# SSS_SOB_REPRO.net
KiCad netlist of a schematic drawn in EAGLE
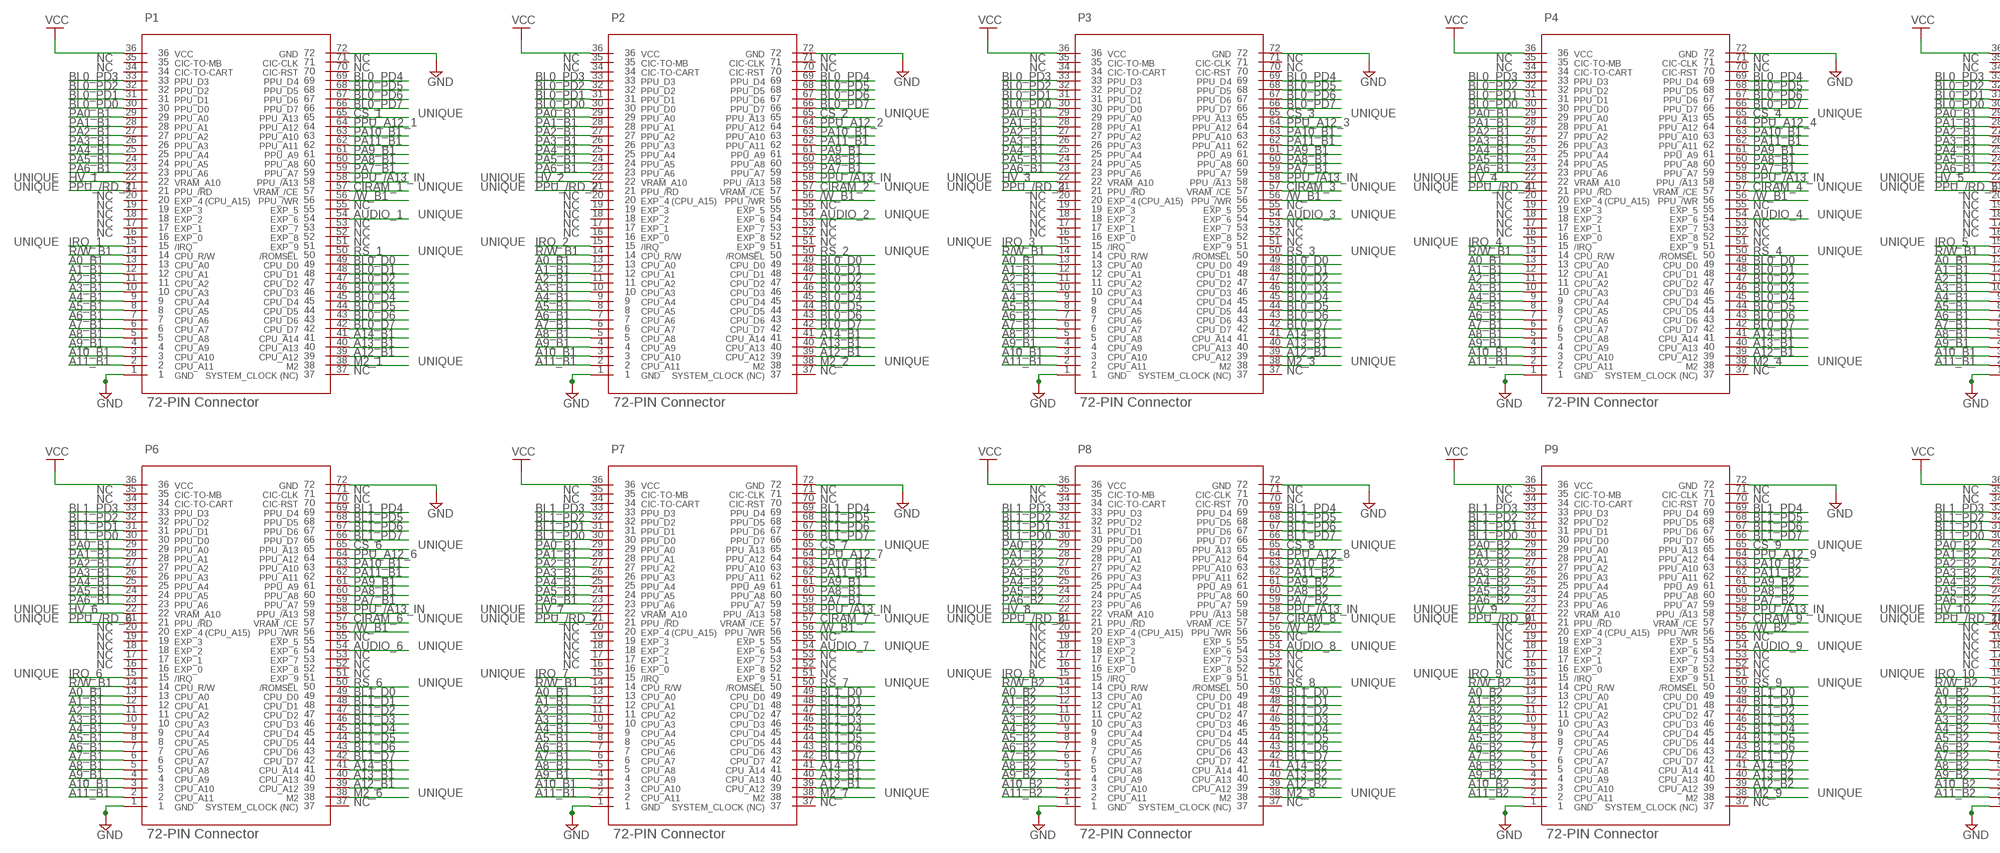
[diagram p0: schematic, sheet 1, part 1 of 3]
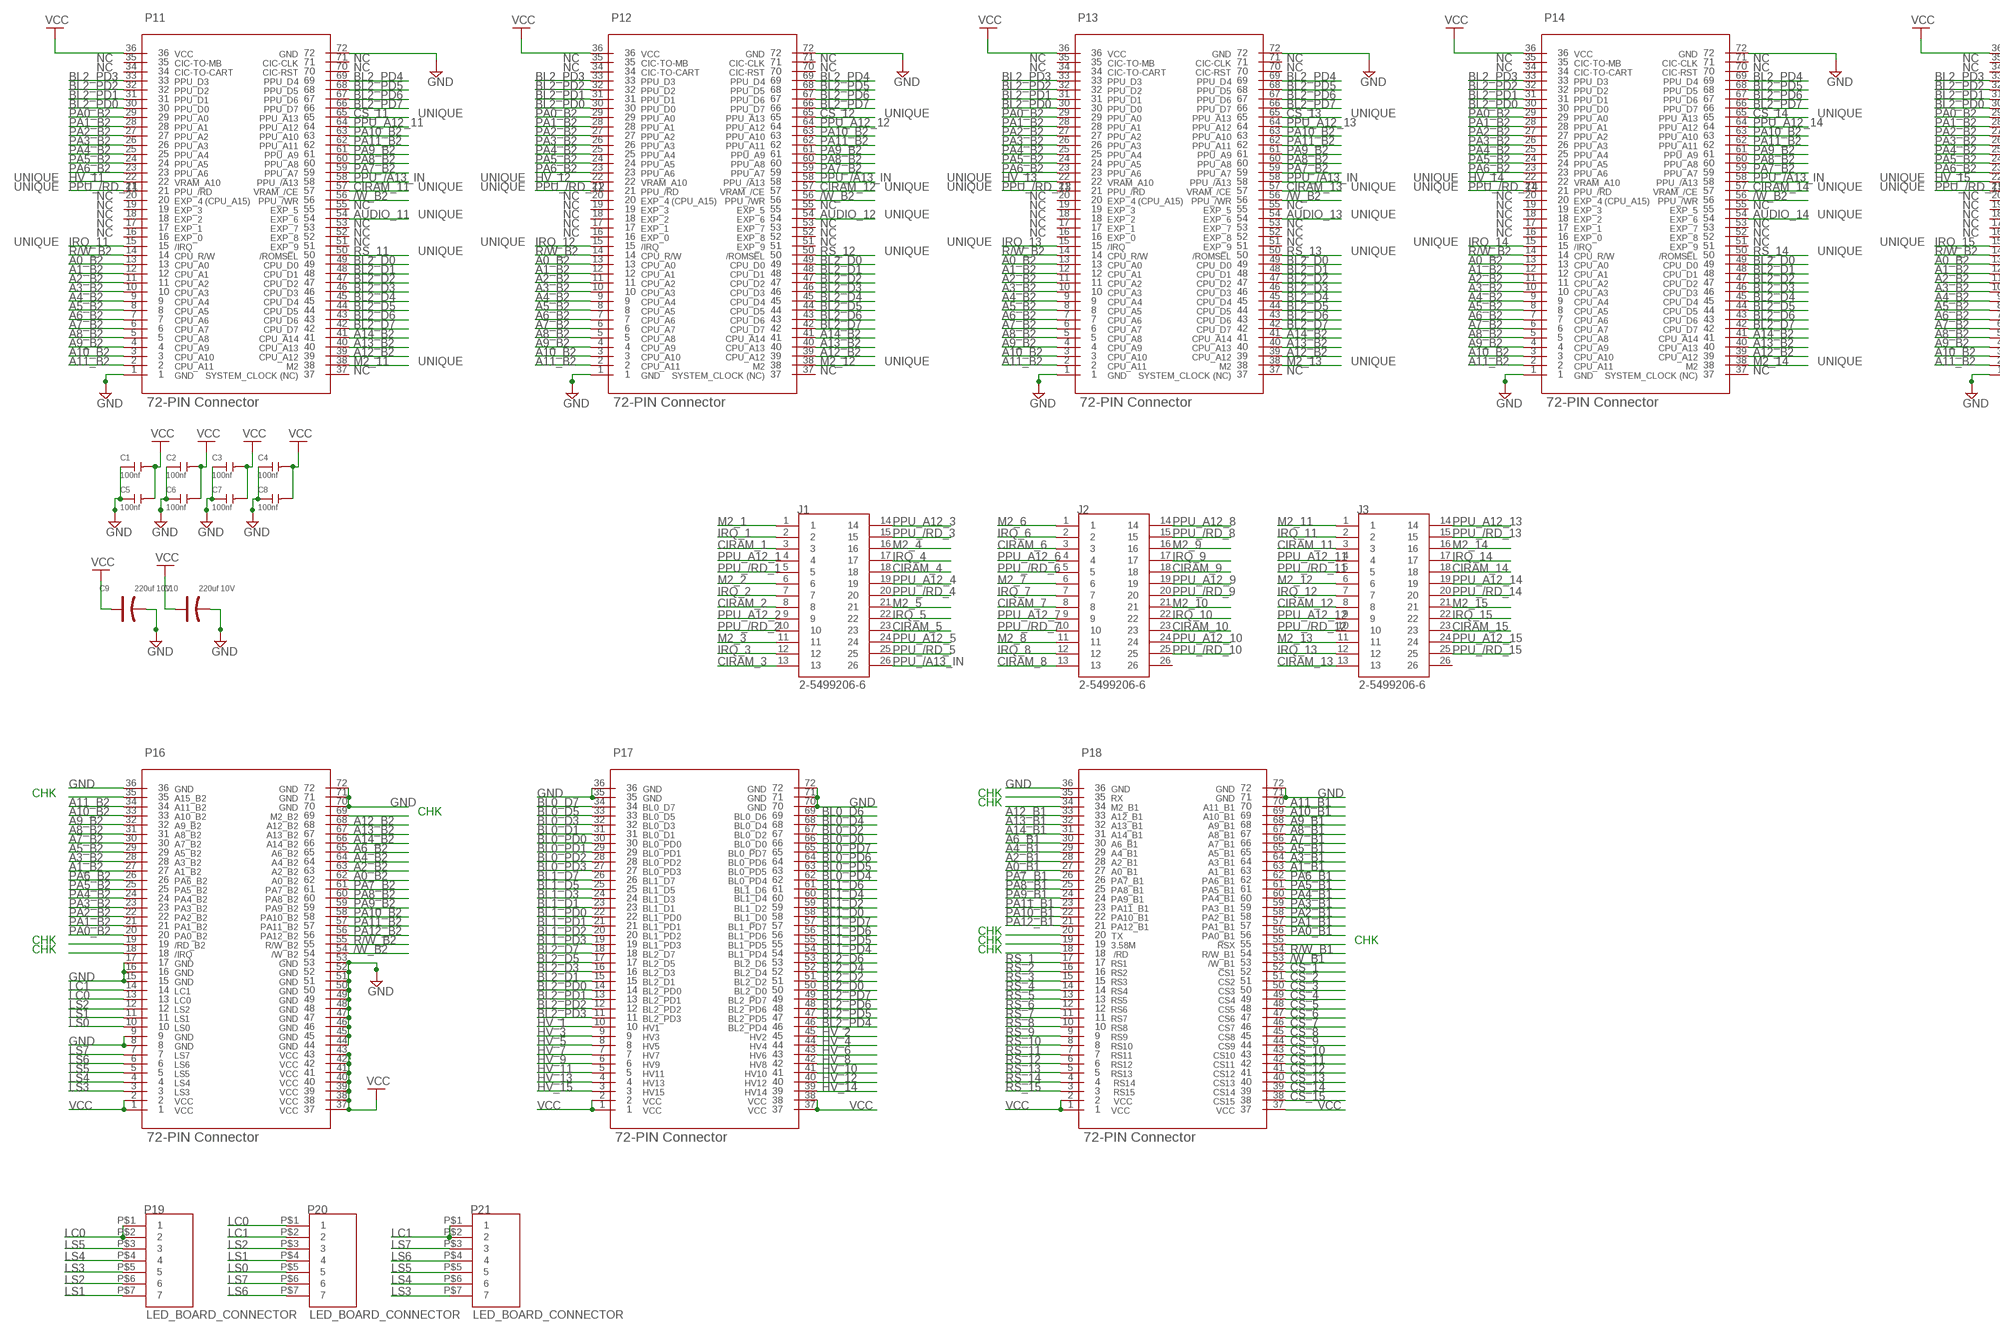
[diagram p1: schematic, sheet 1, part 2 of 3]
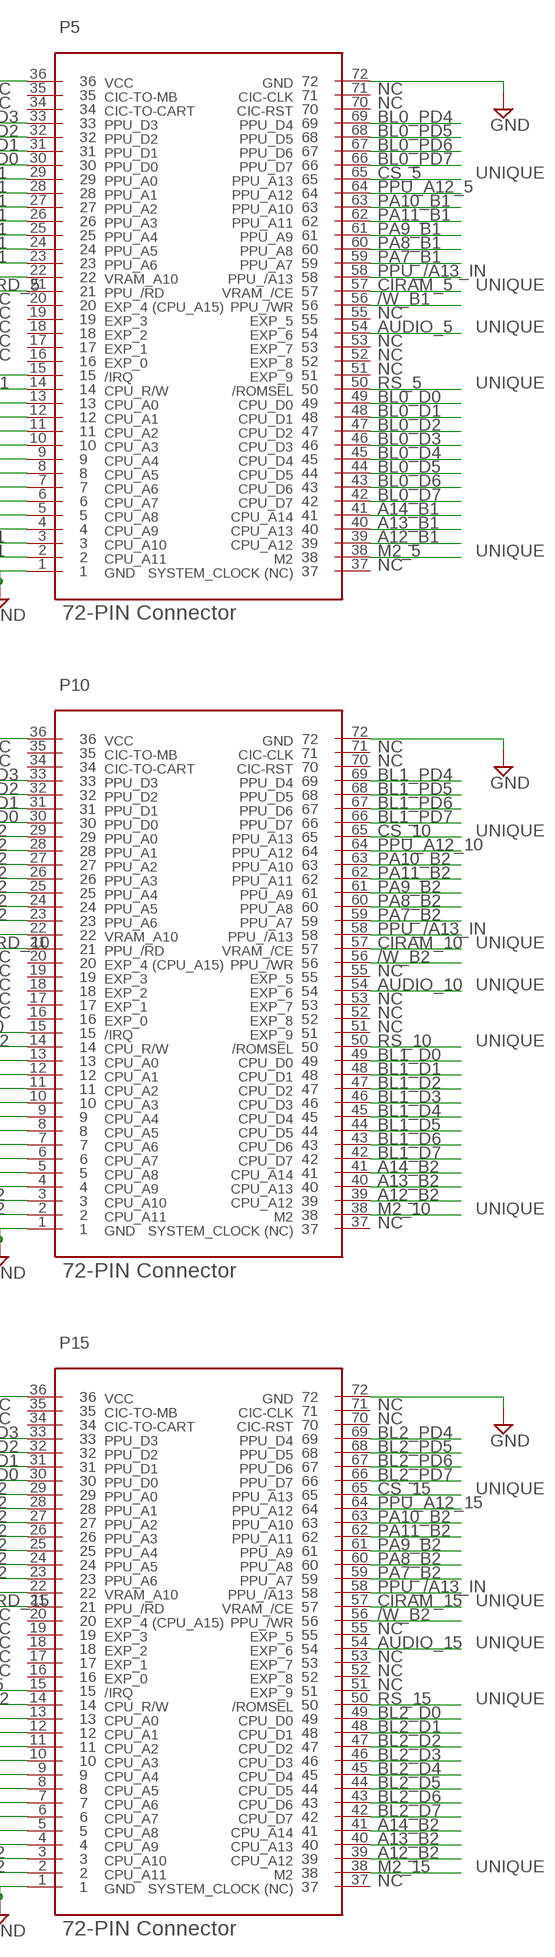
[diagram p2: schematic, sheet 1, part 3 of 3]

(export (version "E")
  (design (tool "Eeschema 10.0.6"))
  (components
    (comp (ref "C1")
      (value "100nf")
      (footprint "eagle-import:C0603")
      (fields (field (name "MPN") "CC0603KRX7R9BB104"))
      (libsource (lib "eagle-import") (part "CERAMIC-100NF-50V-10%-X7R(0603)"))
    )
    (comp (ref "C2")
      (value "100nf")
      (footprint "eagle-import:C0603")
      (fields (field (name "MPN") "CC0603KRX7R9BB104"))
      (libsource (lib "eagle-import") (part "CERAMIC-100NF-50V-10%-X7R(0603)"))
    )
    (comp (ref "C3")
      (value "100nf")
      (footprint "eagle-import:C0603")
      (fields (field (name "MPN") "CC0603KRX7R9BB104"))
      (libsource (lib "eagle-import") (part "CERAMIC-100NF-50V-10%-X7R(0603)"))
    )
    (comp (ref "C4")
      (value "100nf")
      (footprint "eagle-import:C0603")
      (fields (field (name "MPN") "CC0603KRX7R9BB104"))
      (libsource (lib "eagle-import") (part "CERAMIC-100NF-50V-10%-X7R(0603)"))
    )
    (comp (ref "C5")
      (value "100nf")
      (footprint "eagle-import:C0603")
      (fields (field (name "MPN") "CC0603KRX7R9BB104"))
      (libsource (lib "eagle-import") (part "CERAMIC-100NF-50V-10%-X7R(0603)"))
    )
    (comp (ref "C6")
      (value "100nf")
      (footprint "eagle-import:C0603")
      (fields (field (name "MPN") "CC0603KRX7R9BB104"))
      (libsource (lib "eagle-import") (part "CERAMIC-100NF-50V-10%-X7R(0603)"))
    )
    (comp (ref "C7")
      (value "100nf")
      (footprint "eagle-import:C0603")
      (fields (field (name "MPN") "CC0603KRX7R9BB104"))
      (libsource (lib "eagle-import") (part "CERAMIC-100NF-50V-10%-X7R(0603)"))
    )
    (comp (ref "C8")
      (value "100nf")
      (footprint "eagle-import:C0603")
      (fields (field (name "MPN") "CC0603KRX7R9BB104"))
      (libsource (lib "eagle-import") (part "CERAMIC-100NF-50V-10%-X7R(0603)"))
    )
    (comp (ref "C9")
      (value "220uf 10V")
      (footprint "eagle-import:PC-D5.3MM")
      (fields (field (name "MPN") "KS 100uF/16V"))
      (libsource (lib "eagle-import") (part "DIP-ALUMINUM-100UF-16V(D5-H7MM)"))
    )
    (comp (ref "C10")
      (value "220uf 10V")
      (footprint "eagle-import:PC-D5.3MM")
      (fields (field (name "MPN") "KS 100uF/16V"))
      (libsource (lib "eagle-import") (part "DIP-ALUMINUM-100UF-16V(D5-H7MM)"))
    )
    (comp (ref "J1")
      (value "2-5499206-6")
      (footprint "eagle-import:TE_2-5499206-6")
      (fields (field (name "MF") "TE Connectivity"))
      (libsource (lib "eagle-import") (part "2-5499206-6"))
    )
    (comp (ref "J2")
      (value "2-5499206-6")
      (footprint "eagle-import:TE_2-5499206-6")
      (fields (field (name "MF") "TE Connectivity"))
      (libsource (lib "eagle-import") (part "2-5499206-6"))
    )
    (comp (ref "J3")
      (value "2-5499206-6")
      (footprint "eagle-import:TE_2-5499206-6")
      (fields (field (name "MF") "TE Connectivity"))
      (libsource (lib "eagle-import") (part "2-5499206-6"))
    )
    (comp (ref "P1")
      (value "CARTRIDGE_CONNECTOR")
      (footprint "eagle-import:72PIN")
      (libsource (lib "eagle-import") (part "CARTRIDGE_CONNECTOR"))
    )
    (comp (ref "P2")
      (value "CARTRIDGE_CONNECTOR")
      (footprint "eagle-import:72PIN")
      (libsource (lib "eagle-import") (part "CARTRIDGE_CONNECTOR"))
    )
    (comp (ref "P3")
      (value "CARTRIDGE_CONNECTOR")
      (footprint "eagle-import:72PIN")
      (libsource (lib "eagle-import") (part "CARTRIDGE_CONNECTOR"))
    )
    (comp (ref "P4")
      (value "CARTRIDGE_CONNECTOR")
      (footprint "eagle-import:72PIN")
      (libsource (lib "eagle-import") (part "CARTRIDGE_CONNECTOR"))
    )
    (comp (ref "P5")
      (value "CARTRIDGE_CONNECTOR")
      (footprint "eagle-import:72PIN")
      (libsource (lib "eagle-import") (part "CARTRIDGE_CONNECTOR"))
    )
    (comp (ref "P6")
      (value "CARTRIDGE_CONNECTOR")
      (footprint "eagle-import:72PIN")
      (libsource (lib "eagle-import") (part "CARTRIDGE_CONNECTOR"))
    )
    (comp (ref "P7")
      (value "CARTRIDGE_CONNECTOR")
      (footprint "eagle-import:72PIN")
      (libsource (lib "eagle-import") (part "CARTRIDGE_CONNECTOR"))
    )
    (comp (ref "P8")
      (value "CARTRIDGE_CONNECTOR")
      (footprint "eagle-import:72PIN")
      (libsource (lib "eagle-import") (part "CARTRIDGE_CONNECTOR"))
    )
    (comp (ref "P9")
      (value "CARTRIDGE_CONNECTOR")
      (footprint "eagle-import:72PIN")
      (libsource (lib "eagle-import") (part "CARTRIDGE_CONNECTOR"))
    )
    (comp (ref "P10")
      (value "CARTRIDGE_CONNECTOR")
      (footprint "eagle-import:72PIN")
      (libsource (lib "eagle-import") (part "CARTRIDGE_CONNECTOR"))
    )
    (comp (ref "P11")
      (value "CARTRIDGE_CONNECTOR")
      (footprint "eagle-import:72PIN")
      (libsource (lib "eagle-import") (part "CARTRIDGE_CONNECTOR"))
    )
    (comp (ref "P12")
      (value "CARTRIDGE_CONNECTOR")
      (footprint "eagle-import:72PIN")
      (libsource (lib "eagle-import") (part "CARTRIDGE_CONNECTOR"))
    )
    (comp (ref "P13")
      (value "CARTRIDGE_CONNECTOR")
      (footprint "eagle-import:72PIN")
      (libsource (lib "eagle-import") (part "CARTRIDGE_CONNECTOR"))
    )
    (comp (ref "P14")
      (value "CARTRIDGE_CONNECTOR")
      (footprint "eagle-import:72PIN")
      (libsource (lib "eagle-import") (part "CARTRIDGE_CONNECTOR"))
    )
    (comp (ref "P15")
      (value "CARTRIDGE_CONNECTOR")
      (footprint "eagle-import:72PIN")
      (libsource (lib "eagle-import") (part "CARTRIDGE_CONNECTOR"))
    )
    (comp (ref "P16")
      (value "P16_CONNECTOR")
      (footprint "eagle-import:72PIN")
      (libsource (lib "eagle-import") (part "P16_CONNECTOR"))
    )
    (comp (ref "P17")
      (value "P17_CONNECTOR")
      (footprint "eagle-import:72PIN")
      (libsource (lib "eagle-import") (part "P17_CONNECTOR"))
    )
    (comp (ref "P18")
      (value "P18_CONNECTOR")
      (footprint "eagle-import:72PIN")
      (libsource (lib "eagle-import") (part "P18_CONNECTOR"))
    )
    (comp (ref "P19")
      (value "LED_BOARD_CONNECTOR")
      (footprint "eagle-import:7PIN_LED")
      (libsource (lib "eagle-import") (part "LED_BOARD_CONNECTOR"))
    )
    (comp (ref "P20")
      (value "LED_BOARD_CONNECTOR")
      (footprint "eagle-import:7PIN_LED")
      (libsource (lib "eagle-import") (part "LED_BOARD_CONNECTOR"))
    )
    (comp (ref "P21")
      (value "LED_BOARD_CONNECTOR")
      (footprint "eagle-import:7PIN_LED")
      (libsource (lib "eagle-import") (part "LED_BOARD_CONNECTOR"))
    )
  )
  (nets
    (net (code "1") (name "/A0_B1") (class "Default")
      (node (ref "P1") (pin "13") (pinfunction "13_13") (pintype "bidirectional"))
      (node (ref "P18") (pin "27") (pinfunction "27_27") (pintype "bidirectional"))
      (node (ref "P2") (pin "13") (pinfunction "13_13") (pintype "bidirectional"))
      (node (ref "P3") (pin "13") (pinfunction "13_13") (pintype "bidirectional"))
      (node (ref "P4") (pin "13") (pinfunction "13_13") (pintype "bidirectional"))
      (node (ref "P5") (pin "13") (pinfunction "13_13") (pintype "bidirectional"))
      (node (ref "P6") (pin "13") (pinfunction "13_13") (pintype "bidirectional"))
      (node (ref "P7") (pin "13") (pinfunction "13_13") (pintype "bidirectional"))
    )
    (net (code "2") (name "/A0_B2") (class "Default")
      (node (ref "P10") (pin "13") (pinfunction "13_13") (pintype "bidirectional"))
      (node (ref "P11") (pin "13") (pinfunction "13_13") (pintype "bidirectional"))
      (node (ref "P12") (pin "13") (pinfunction "13_13") (pintype "bidirectional"))
      (node (ref "P13") (pin "13") (pinfunction "13_13") (pintype "bidirectional"))
      (node (ref "P14") (pin "13") (pinfunction "13_13") (pintype "bidirectional"))
      (node (ref "P15") (pin "13") (pinfunction "13_13") (pintype "bidirectional"))
      (node (ref "P16") (pin "62") (pinfunction "62_62") (pintype "bidirectional"))
      (node (ref "P8") (pin "13") (pinfunction "13_13") (pintype "bidirectional"))
      (node (ref "P9") (pin "13") (pinfunction "13_13") (pintype "bidirectional"))
    )
    (net (code "3") (name "/A1_B1") (class "Default")
      (node (ref "P1") (pin "12") (pinfunction "12_12") (pintype "bidirectional"))
      (node (ref "P18") (pin "63") (pinfunction "63_63") (pintype "bidirectional"))
      (node (ref "P2") (pin "12") (pinfunction "12_12") (pintype "bidirectional"))
      (node (ref "P3") (pin "12") (pinfunction "12_12") (pintype "bidirectional"))
      (node (ref "P4") (pin "12") (pinfunction "12_12") (pintype "bidirectional"))
      (node (ref "P5") (pin "12") (pinfunction "12_12") (pintype "bidirectional"))
      (node (ref "P6") (pin "12") (pinfunction "12_12") (pintype "bidirectional"))
      (node (ref "P7") (pin "12") (pinfunction "12_12") (pintype "bidirectional"))
    )
    (net (code "4") (name "/A1_B2") (class "Default")
      (node (ref "P10") (pin "12") (pinfunction "12_12") (pintype "bidirectional"))
      (node (ref "P11") (pin "12") (pinfunction "12_12") (pintype "bidirectional"))
      (node (ref "P12") (pin "12") (pinfunction "12_12") (pintype "bidirectional"))
      (node (ref "P13") (pin "12") (pinfunction "12_12") (pintype "bidirectional"))
      (node (ref "P14") (pin "12") (pinfunction "12_12") (pintype "bidirectional"))
      (node (ref "P15") (pin "12") (pinfunction "12_12") (pintype "bidirectional"))
      (node (ref "P16") (pin "27") (pinfunction "27_27") (pintype "bidirectional"))
      (node (ref "P8") (pin "12") (pinfunction "12_12") (pintype "bidirectional"))
      (node (ref "P9") (pin "12") (pinfunction "12_12") (pintype "bidirectional"))
    )
    (net (code "5") (name "/A2_B1") (class "Default")
      (node (ref "P1") (pin "11") (pinfunction "11_11") (pintype "bidirectional"))
      (node (ref "P18") (pin "28") (pinfunction "28_28") (pintype "bidirectional"))
      (node (ref "P2") (pin "11") (pinfunction "11_11") (pintype "bidirectional"))
      (node (ref "P3") (pin "11") (pinfunction "11_11") (pintype "bidirectional"))
      (node (ref "P4") (pin "11") (pinfunction "11_11") (pintype "bidirectional"))
      (node (ref "P5") (pin "11") (pinfunction "11_11") (pintype "bidirectional"))
      (node (ref "P6") (pin "11") (pinfunction "11_11") (pintype "bidirectional"))
      (node (ref "P7") (pin "11") (pinfunction "11_11") (pintype "bidirectional"))
    )
    (net (code "6") (name "/A2_B2") (class "Default")
      (node (ref "P10") (pin "11") (pinfunction "11_11") (pintype "bidirectional"))
      (node (ref "P11") (pin "11") (pinfunction "11_11") (pintype "bidirectional"))
      (node (ref "P12") (pin "11") (pinfunction "11_11") (pintype "bidirectional"))
      (node (ref "P13") (pin "11") (pinfunction "11_11") (pintype "bidirectional"))
      (node (ref "P14") (pin "11") (pinfunction "11_11") (pintype "bidirectional"))
      (node (ref "P15") (pin "11") (pinfunction "11_11") (pintype "bidirectional"))
      (node (ref "P16") (pin "63") (pinfunction "63_63") (pintype "bidirectional"))
      (node (ref "P8") (pin "11") (pinfunction "11_11") (pintype "bidirectional"))
      (node (ref "P9") (pin "11") (pinfunction "11_11") (pintype "bidirectional"))
    )
    (net (code "7") (name "/A3_B1") (class "Default")
      (node (ref "P1") (pin "10") (pinfunction "10_10") (pintype "bidirectional"))
      (node (ref "P18") (pin "64") (pinfunction "64_64") (pintype "bidirectional"))
      (node (ref "P2") (pin "10") (pinfunction "10_10") (pintype "bidirectional"))
      (node (ref "P3") (pin "10") (pinfunction "10_10") (pintype "bidirectional"))
      (node (ref "P4") (pin "10") (pinfunction "10_10") (pintype "bidirectional"))
      (node (ref "P5") (pin "10") (pinfunction "10_10") (pintype "bidirectional"))
      (node (ref "P6") (pin "10") (pinfunction "10_10") (pintype "bidirectional"))
      (node (ref "P7") (pin "10") (pinfunction "10_10") (pintype "bidirectional"))
    )
    (net (code "8") (name "/A3_B2") (class "Default")
      (node (ref "P10") (pin "10") (pinfunction "10_10") (pintype "bidirectional"))
      (node (ref "P11") (pin "10") (pinfunction "10_10") (pintype "bidirectional"))
      (node (ref "P12") (pin "10") (pinfunction "10_10") (pintype "bidirectional"))
      (node (ref "P13") (pin "10") (pinfunction "10_10") (pintype "bidirectional"))
      (node (ref "P14") (pin "10") (pinfunction "10_10") (pintype "bidirectional"))
      (node (ref "P15") (pin "10") (pinfunction "10_10") (pintype "bidirectional"))
      (node (ref "P16") (pin "28") (pinfunction "28_28") (pintype "bidirectional"))
      (node (ref "P8") (pin "10") (pinfunction "10_10") (pintype "bidirectional"))
      (node (ref "P9") (pin "10") (pinfunction "10_10") (pintype "bidirectional"))
    )
    (net (code "9") (name "/A4_B1") (class "Default")
      (node (ref "P1") (pin "9") (pinfunction "9_9") (pintype "bidirectional"))
      (node (ref "P18") (pin "29") (pinfunction "29_29") (pintype "bidirectional"))
      (node (ref "P2") (pin "9") (pinfunction "9_9") (pintype "bidirectional"))
      (node (ref "P3") (pin "9") (pinfunction "9_9") (pintype "bidirectional"))
      (node (ref "P4") (pin "9") (pinfunction "9_9") (pintype "bidirectional"))
      (node (ref "P5") (pin "9") (pinfunction "9_9") (pintype "bidirectional"))
      (node (ref "P6") (pin "9") (pinfunction "9_9") (pintype "bidirectional"))
      (node (ref "P7") (pin "9") (pinfunction "9_9") (pintype "bidirectional"))
    )
    (net (code "10") (name "/A4_B2") (class "Default")
      (node (ref "P10") (pin "9") (pinfunction "9_9") (pintype "bidirectional"))
      (node (ref "P11") (pin "9") (pinfunction "9_9") (pintype "bidirectional"))
      (node (ref "P12") (pin "9") (pinfunction "9_9") (pintype "bidirectional"))
      (node (ref "P13") (pin "9") (pinfunction "9_9") (pintype "bidirectional"))
      (node (ref "P14") (pin "9") (pinfunction "9_9") (pintype "bidirectional"))
      (node (ref "P15") (pin "9") (pinfunction "9_9") (pintype "bidirectional"))
      (node (ref "P16") (pin "64") (pinfunction "64_64") (pintype "bidirectional"))
      (node (ref "P8") (pin "9") (pinfunction "9_9") (pintype "bidirectional"))
      (node (ref "P9") (pin "9") (pinfunction "9_9") (pintype "bidirectional"))
    )
    (net (code "11") (name "/A5_B1") (class "Default")
      (node (ref "P1") (pin "8") (pinfunction "8_8") (pintype "bidirectional"))
      (node (ref "P18") (pin "65") (pinfunction "65_65") (pintype "bidirectional"))
      (node (ref "P2") (pin "8") (pinfunction "8_8") (pintype "bidirectional"))
      (node (ref "P3") (pin "8") (pinfunction "8_8") (pintype "bidirectional"))
      (node (ref "P4") (pin "8") (pinfunction "8_8") (pintype "bidirectional"))
      (node (ref "P5") (pin "8") (pinfunction "8_8") (pintype "bidirectional"))
      (node (ref "P6") (pin "8") (pinfunction "8_8") (pintype "bidirectional"))
      (node (ref "P7") (pin "8") (pinfunction "8_8") (pintype "bidirectional"))
    )
    (net (code "12") (name "/A5_B2") (class "Default")
      (node (ref "P10") (pin "8") (pinfunction "8_8") (pintype "bidirectional"))
      (node (ref "P11") (pin "8") (pinfunction "8_8") (pintype "bidirectional"))
      (node (ref "P12") (pin "8") (pinfunction "8_8") (pintype "bidirectional"))
      (node (ref "P13") (pin "8") (pinfunction "8_8") (pintype "bidirectional"))
      (node (ref "P14") (pin "8") (pinfunction "8_8") (pintype "bidirectional"))
      (node (ref "P15") (pin "8") (pinfunction "8_8") (pintype "bidirectional"))
      (node (ref "P16") (pin "29") (pinfunction "29_29") (pintype "bidirectional"))
      (node (ref "P8") (pin "8") (pinfunction "8_8") (pintype "bidirectional"))
      (node (ref "P9") (pin "8") (pinfunction "8_8") (pintype "bidirectional"))
    )
    (net (code "13") (name "/A6_B1") (class "Default")
      (node (ref "P1") (pin "7") (pinfunction "7_7") (pintype "bidirectional"))
      (node (ref "P18") (pin "30") (pinfunction "30_30") (pintype "bidirectional"))
      (node (ref "P2") (pin "7") (pinfunction "7_7") (pintype "bidirectional"))
      (node (ref "P3") (pin "7") (pinfunction "7_7") (pintype "bidirectional"))
      (node (ref "P4") (pin "7") (pinfunction "7_7") (pintype "bidirectional"))
      (node (ref "P5") (pin "7") (pinfunction "7_7") (pintype "bidirectional"))
      (node (ref "P6") (pin "7") (pinfunction "7_7") (pintype "bidirectional"))
      (node (ref "P7") (pin "7") (pinfunction "7_7") (pintype "bidirectional"))
    )
    (net (code "14") (name "/A6_B2") (class "Default")
      (node (ref "P10") (pin "7") (pinfunction "7_7") (pintype "bidirectional"))
      (node (ref "P11") (pin "7") (pinfunction "7_7") (pintype "bidirectional"))
      (node (ref "P12") (pin "7") (pinfunction "7_7") (pintype "bidirectional"))
      (node (ref "P13") (pin "7") (pinfunction "7_7") (pintype "bidirectional"))
      (node (ref "P14") (pin "7") (pinfunction "7_7") (pintype "bidirectional"))
      (node (ref "P15") (pin "7") (pinfunction "7_7") (pintype "bidirectional"))
      (node (ref "P16") (pin "65") (pinfunction "65_65") (pintype "bidirectional"))
      (node (ref "P8") (pin "7") (pinfunction "7_7") (pintype "bidirectional"))
      (node (ref "P9") (pin "7") (pinfunction "7_7") (pintype "bidirectional"))
    )
    (net (code "15") (name "/A7_B1") (class "Default")
      (node (ref "P1") (pin "6") (pinfunction "6_6") (pintype "bidirectional"))
      (node (ref "P18") (pin "66") (pinfunction "66_66") (pintype "bidirectional"))
      (node (ref "P2") (pin "6") (pinfunction "6_6") (pintype "bidirectional"))
      (node (ref "P3") (pin "6") (pinfunction "6_6") (pintype "bidirectional"))
      (node (ref "P4") (pin "6") (pinfunction "6_6") (pintype "bidirectional"))
      (node (ref "P5") (pin "6") (pinfunction "6_6") (pintype "bidirectional"))
      (node (ref "P6") (pin "6") (pinfunction "6_6") (pintype "bidirectional"))
      (node (ref "P7") (pin "6") (pinfunction "6_6") (pintype "bidirectional"))
    )
    (net (code "16") (name "/A7_B2") (class "Default")
      (node (ref "P10") (pin "6") (pinfunction "6_6") (pintype "bidirectional"))
      (node (ref "P11") (pin "6") (pinfunction "6_6") (pintype "bidirectional"))
      (node (ref "P12") (pin "6") (pinfunction "6_6") (pintype "bidirectional"))
      (node (ref "P13") (pin "6") (pinfunction "6_6") (pintype "bidirectional"))
      (node (ref "P14") (pin "6") (pinfunction "6_6") (pintype "bidirectional"))
      (node (ref "P15") (pin "6") (pinfunction "6_6") (pintype "bidirectional"))
      (node (ref "P16") (pin "30") (pinfunction "30_30") (pintype "bidirectional"))
      (node (ref "P8") (pin "6") (pinfunction "6_6") (pintype "bidirectional"))
      (node (ref "P9") (pin "6") (pinfunction "6_6") (pintype "bidirectional"))
    )
    (net (code "17") (name "/A8_B1") (class "Default")
      (node (ref "P1") (pin "5") (pinfunction "5_5") (pintype "bidirectional"))
      (node (ref "P18") (pin "67") (pinfunction "67_67") (pintype "bidirectional"))
      (node (ref "P2") (pin "5") (pinfunction "5_5") (pintype "bidirectional"))
      (node (ref "P3") (pin "5") (pinfunction "5_5") (pintype "bidirectional"))
      (node (ref "P4") (pin "5") (pinfunction "5_5") (pintype "bidirectional"))
      (node (ref "P5") (pin "5") (pinfunction "5_5") (pintype "bidirectional"))
      (node (ref "P6") (pin "5") (pinfunction "5_5") (pintype "bidirectional"))
      (node (ref "P7") (pin "5") (pinfunction "5_5") (pintype "bidirectional"))
    )
    (net (code "18") (name "/A8_B2") (class "Default")
      (node (ref "P10") (pin "5") (pinfunction "5_5") (pintype "bidirectional"))
      (node (ref "P11") (pin "5") (pinfunction "5_5") (pintype "bidirectional"))
      (node (ref "P12") (pin "5") (pinfunction "5_5") (pintype "bidirectional"))
      (node (ref "P13") (pin "5") (pinfunction "5_5") (pintype "bidirectional"))
      (node (ref "P14") (pin "5") (pinfunction "5_5") (pintype "bidirectional"))
      (node (ref "P15") (pin "5") (pinfunction "5_5") (pintype "bidirectional"))
      (node (ref "P16") (pin "31") (pinfunction "31_31") (pintype "bidirectional"))
      (node (ref "P8") (pin "5") (pinfunction "5_5") (pintype "bidirectional"))
      (node (ref "P9") (pin "5") (pinfunction "5_5") (pintype "bidirectional"))
    )
    (net (code "19") (name "/A9_B1") (class "Default")
      (node (ref "P1") (pin "4") (pinfunction "4_4") (pintype "bidirectional"))
      (node (ref "P18") (pin "68") (pinfunction "68_68") (pintype "bidirectional"))
      (node (ref "P2") (pin "4") (pinfunction "4_4") (pintype "bidirectional"))
      (node (ref "P3") (pin "4") (pinfunction "4_4") (pintype "bidirectional"))
      (node (ref "P4") (pin "4") (pinfunction "4_4") (pintype "bidirectional"))
      (node (ref "P5") (pin "4") (pinfunction "4_4") (pintype "bidirectional"))
      (node (ref "P6") (pin "4") (pinfunction "4_4") (pintype "bidirectional"))
      (node (ref "P7") (pin "4") (pinfunction "4_4") (pintype "bidirectional"))
    )
    (net (code "20") (name "/A9_B2") (class "Default")
      (node (ref "P10") (pin "4") (pinfunction "4_4") (pintype "bidirectional"))
      (node (ref "P11") (pin "4") (pinfunction "4_4") (pintype "bidirectional"))
      (node (ref "P12") (pin "4") (pinfunction "4_4") (pintype "bidirectional"))
      (node (ref "P13") (pin "4") (pinfunction "4_4") (pintype "bidirectional"))
      (node (ref "P14") (pin "4") (pinfunction "4_4") (pintype "bidirectional"))
      (node (ref "P15") (pin "4") (pinfunction "4_4") (pintype "bidirectional"))
      (node (ref "P16") (pin "32") (pinfunction "32_32") (pintype "bidirectional"))
      (node (ref "P8") (pin "4") (pinfunction "4_4") (pintype "bidirectional"))
      (node (ref "P9") (pin "4") (pinfunction "4_4") (pintype "bidirectional"))
    )
    (net (code "21") (name "/A10_B1") (class "Default")
      (node (ref "P1") (pin "3") (pinfunction "3_3") (pintype "bidirectional"))
      (node (ref "P18") (pin "69") (pinfunction "69_69") (pintype "bidirectional"))
      (node (ref "P2") (pin "3") (pinfunction "3_3") (pintype "bidirectional"))
      (node (ref "P3") (pin "3") (pinfunction "3_3") (pintype "bidirectional"))
      (node (ref "P4") (pin "3") (pinfunction "3_3") (pintype "bidirectional"))
      (node (ref "P5") (pin "3") (pinfunction "3_3") (pintype "bidirectional"))
      (node (ref "P6") (pin "3") (pinfunction "3_3") (pintype "bidirectional"))
      (node (ref "P7") (pin "3") (pinfunction "3_3") (pintype "bidirectional"))
    )
    (net (code "22") (name "/A10_B2") (class "Default")
      (node (ref "P10") (pin "3") (pinfunction "3_3") (pintype "bidirectional"))
      (node (ref "P11") (pin "3") (pinfunction "3_3") (pintype "bidirectional"))
      (node (ref "P12") (pin "3") (pinfunction "3_3") (pintype "bidirectional"))
      (node (ref "P13") (pin "3") (pinfunction "3_3") (pintype "bidirectional"))
      (node (ref "P14") (pin "3") (pinfunction "3_3") (pintype "bidirectional"))
      (node (ref "P15") (pin "3") (pinfunction "3_3") (pintype "bidirectional"))
      (node (ref "P16") (pin "33") (pinfunction "33_33") (pintype "bidirectional"))
      (node (ref "P8") (pin "3") (pinfunction "3_3") (pintype "bidirectional"))
      (node (ref "P9") (pin "3") (pinfunction "3_3") (pintype "bidirectional"))
    )
    (net (code "23") (name "/A11_B1") (class "Default")
      (node (ref "P1") (pin "2") (pinfunction "2_2") (pintype "bidirectional"))
      (node (ref "P18") (pin "70") (pinfunction "70_70") (pintype "bidirectional"))
      (node (ref "P2") (pin "2") (pinfunction "2_2") (pintype "bidirectional"))
      (node (ref "P3") (pin "2") (pinfunction "2_2") (pintype "bidirectional"))
      (node (ref "P4") (pin "2") (pinfunction "2_2") (pintype "bidirectional"))
      (node (ref "P5") (pin "2") (pinfunction "2_2") (pintype "bidirectional"))
      (node (ref "P6") (pin "2") (pinfunction "2_2") (pintype "bidirectional"))
      (node (ref "P7") (pin "2") (pinfunction "2_2") (pintype "bidirectional"))
    )
    (net (code "24") (name "/A11_B2") (class "Default")
      (node (ref "P10") (pin "2") (pinfunction "2_2") (pintype "bidirectional"))
      (node (ref "P11") (pin "2") (pinfunction "2_2") (pintype "bidirectional"))
      (node (ref "P12") (pin "2") (pinfunction "2_2") (pintype "bidirectional"))
      (node (ref "P13") (pin "2") (pinfunction "2_2") (pintype "bidirectional"))
      (node (ref "P14") (pin "2") (pinfunction "2_2") (pintype "bidirectional"))
      (node (ref "P15") (pin "2") (pinfunction "2_2") (pintype "bidirectional"))
      (node (ref "P16") (pin "34") (pinfunction "34_34") (pintype "bidirectional"))
      (node (ref "P8") (pin "2") (pinfunction "2_2") (pintype "bidirectional"))
      (node (ref "P9") (pin "2") (pinfunction "2_2") (pintype "bidirectional"))
    )
    (net (code "25") (name "/A12_B1") (class "Default")
      (node (ref "P1") (pin "39") (pinfunction "39_39") (pintype "bidirectional"))
      (node (ref "P18") (pin "33") (pinfunction "33_33") (pintype "bidirectional"))
      (node (ref "P2") (pin "39") (pinfunction "39_39") (pintype "bidirectional"))
      (node (ref "P3") (pin "39") (pinfunction "39_39") (pintype "bidirectional"))
      (node (ref "P4") (pin "39") (pinfunction "39_39") (pintype "bidirectional"))
      (node (ref "P5") (pin "39") (pinfunction "39_39") (pintype "bidirectional"))
      (node (ref "P6") (pin "39") (pinfunction "39_39") (pintype "bidirectional"))
      (node (ref "P7") (pin "39") (pinfunction "39_39") (pintype "bidirectional"))
    )
    (net (code "26") (name "/A12_B2") (class "Default")
      (node (ref "P10") (pin "39") (pinfunction "39_39") (pintype "bidirectional"))
      (node (ref "P11") (pin "39") (pinfunction "39_39") (pintype "bidirectional"))
      (node (ref "P12") (pin "39") (pinfunction "39_39") (pintype "bidirectional"))
      (node (ref "P13") (pin "39") (pinfunction "39_39") (pintype "bidirectional"))
      (node (ref "P14") (pin "39") (pinfunction "39_39") (pintype "bidirectional"))
      (node (ref "P15") (pin "39") (pinfunction "39_39") (pintype "bidirectional"))
      (node (ref "P16") (pin "68") (pinfunction "68_68") (pintype "bidirectional"))
      (node (ref "P8") (pin "39") (pinfunction "39_39") (pintype "bidirectional"))
      (node (ref "P9") (pin "39") (pinfunction "39_39") (pintype "bidirectional"))
    )
    (net (code "27") (name "/A13_B1") (class "Default")
      (node (ref "P1") (pin "40") (pinfunction "40_40") (pintype "bidirectional"))
      (node (ref "P18") (pin "32") (pinfunction "32_32") (pintype "bidirectional"))
      (node (ref "P2") (pin "40") (pinfunction "40_40") (pintype "bidirectional"))
      (node (ref "P3") (pin "40") (pinfunction "40_40") (pintype "bidirectional"))
      (node (ref "P4") (pin "40") (pinfunction "40_40") (pintype "bidirectional"))
      (node (ref "P5") (pin "40") (pinfunction "40_40") (pintype "bidirectional"))
      (node (ref "P6") (pin "40") (pinfunction "40_40") (pintype "bidirectional"))
      (node (ref "P7") (pin "40") (pinfunction "40_40") (pintype "bidirectional"))
    )
    (net (code "28") (name "/A13_B2") (class "Default")
      (node (ref "P10") (pin "40") (pinfunction "40_40") (pintype "bidirectional"))
      (node (ref "P11") (pin "40") (pinfunction "40_40") (pintype "bidirectional"))
      (node (ref "P12") (pin "40") (pinfunction "40_40") (pintype "bidirectional"))
      (node (ref "P13") (pin "40") (pinfunction "40_40") (pintype "bidirectional"))
      (node (ref "P14") (pin "40") (pinfunction "40_40") (pintype "bidirectional"))
      (node (ref "P15") (pin "40") (pinfunction "40_40") (pintype "bidirectional"))
      (node (ref "P16") (pin "67") (pinfunction "67_67") (pintype "bidirectional"))
      (node (ref "P8") (pin "40") (pinfunction "40_40") (pintype "bidirectional"))
      (node (ref "P9") (pin "40") (pinfunction "40_40") (pintype "bidirectional"))
    )
    (net (code "29") (name "/A14_B1") (class "Default")
      (node (ref "P1") (pin "41") (pinfunction "41_41") (pintype "bidirectional"))
      (node (ref "P18") (pin "31") (pinfunction "31_31") (pintype "bidirectional"))
      (node (ref "P2") (pin "41") (pinfunction "41_41") (pintype "bidirectional"))
      (node (ref "P3") (pin "41") (pinfunction "41_41") (pintype "bidirectional"))
      (node (ref "P4") (pin "41") (pinfunction "41_41") (pintype "bidirectional"))
      (node (ref "P5") (pin "41") (pinfunction "41_41") (pintype "bidirectional"))
      (node (ref "P6") (pin "41") (pinfunction "41_41") (pintype "bidirectional"))
      (node (ref "P7") (pin "41") (pinfunction "41_41") (pintype "bidirectional"))
    )
    (net (code "30") (name "/A14_B2") (class "Default")
      (node (ref "P10") (pin "41") (pinfunction "41_41") (pintype "bidirectional"))
      (node (ref "P11") (pin "41") (pinfunction "41_41") (pintype "bidirectional"))
      (node (ref "P12") (pin "41") (pinfunction "41_41") (pintype "bidirectional"))
      (node (ref "P13") (pin "41") (pinfunction "41_41") (pintype "bidirectional"))
      (node (ref "P14") (pin "41") (pinfunction "41_41") (pintype "bidirectional"))
      (node (ref "P15") (pin "41") (pinfunction "41_41") (pintype "bidirectional"))
      (node (ref "P16") (pin "66") (pinfunction "66_66") (pintype "bidirectional"))
      (node (ref "P8") (pin "41") (pinfunction "41_41") (pintype "bidirectional"))
      (node (ref "P9") (pin "41") (pinfunction "41_41") (pintype "bidirectional"))
    )
    (net (code "31") (name "/AUDIO_1") (class "Default")
      (node (ref "P1") (pin "54") (pinfunction "54_54") (pintype "bidirectional"))
    )
    (net (code "32") (name "/AUDIO_2") (class "Default")
      (node (ref "P2") (pin "54") (pinfunction "54_54") (pintype "bidirectional"))
    )
    (net (code "33") (name "/AUDIO_3") (class "Default")
      (node (ref "P3") (pin "54") (pinfunction "54_54") (pintype "bidirectional"))
    )
    (net (code "34") (name "/AUDIO_4") (class "Default")
      (node (ref "P4") (pin "54") (pinfunction "54_54") (pintype "bidirectional"))
    )
    (net (code "35") (name "/AUDIO_5") (class "Default")
      (node (ref "P5") (pin "54") (pinfunction "54_54") (pintype "bidirectional"))
    )
    (net (code "36") (name "/AUDIO_6") (class "Default")
      (node (ref "P6") (pin "54") (pinfunction "54_54") (pintype "bidirectional"))
    )
    (net (code "37") (name "/AUDIO_7") (class "Default")
      (node (ref "P7") (pin "54") (pinfunction "54_54") (pintype "bidirectional"))
    )
    (net (code "38") (name "/AUDIO_8") (class "Default")
      (node (ref "P8") (pin "54") (pinfunction "54_54") (pintype "bidirectional"))
    )
    (net (code "39") (name "/AUDIO_9") (class "Default")
      (node (ref "P9") (pin "54") (pinfunction "54_54") (pintype "bidirectional"))
    )
    (net (code "40") (name "/AUDIO_10") (class "Default")
      (node (ref "P10") (pin "54") (pinfunction "54_54") (pintype "bidirectional"))
    )
    (net (code "41") (name "/AUDIO_11") (class "Default")
      (node (ref "P11") (pin "54") (pinfunction "54_54") (pintype "bidirectional"))
    )
    (net (code "42") (name "/AUDIO_12") (class "Default")
      (node (ref "P12") (pin "54") (pinfunction "54_54") (pintype "bidirectional"))
    )
    (net (code "43") (name "/AUDIO_13") (class "Default")
      (node (ref "P13") (pin "54") (pinfunction "54_54") (pintype "bidirectional"))
    )
    (net (code "44") (name "/AUDIO_14") (class "Default")
      (node (ref "P14") (pin "54") (pinfunction "54_54") (pintype "bidirectional"))
    )
    (net (code "45") (name "/AUDIO_15") (class "Default")
      (node (ref "P15") (pin "54") (pinfunction "54_54") (pintype "bidirectional"))
    )
    (net (code "46") (name "/BL0_D0") (class "Default")
      (node (ref "P1") (pin "49") (pinfunction "49_49") (pintype "bidirectional"))
      (node (ref "P17") (pin "66") (pinfunction "66_66") (pintype "bidirectional"))
      (node (ref "P2") (pin "49") (pinfunction "49_49") (pintype "bidirectional"))
      (node (ref "P3") (pin "49") (pinfunction "49_49") (pintype "bidirectional"))
      (node (ref "P4") (pin "49") (pinfunction "49_49") (pintype "bidirectional"))
      (node (ref "P5") (pin "49") (pinfunction "49_49") (pintype "bidirectional"))
    )
    (net (code "47") (name "/BL0_D1") (class "Default")
      (node (ref "P1") (pin "48") (pinfunction "48_48") (pintype "bidirectional"))
      (node (ref "P17") (pin "31") (pinfunction "31_31") (pintype "bidirectional"))
      (node (ref "P2") (pin "48") (pinfunction "48_48") (pintype "bidirectional"))
      (node (ref "P3") (pin "48") (pinfunction "48_48") (pintype "bidirectional"))
      (node (ref "P4") (pin "48") (pinfunction "48_48") (pintype "bidirectional"))
      (node (ref "P5") (pin "48") (pinfunction "48_48") (pintype "bidirectional"))
    )
    (net (code "48") (name "/BL0_D2") (class "Default")
      (node (ref "P1") (pin "47") (pinfunction "47_47") (pintype "bidirectional"))
      (node (ref "P17") (pin "67") (pinfunction "67_67") (pintype "bidirectional"))
      (node (ref "P2") (pin "47") (pinfunction "47_47") (pintype "bidirectional"))
      (node (ref "P3") (pin "47") (pinfunction "47_47") (pintype "bidirectional"))
      (node (ref "P4") (pin "47") (pinfunction "47_47") (pintype "bidirectional"))
      (node (ref "P5") (pin "47") (pinfunction "47_47") (pintype "bidirectional"))
    )
    (net (code "49") (name "/BL0_D3") (class "Default")
      (node (ref "P1") (pin "46") (pinfunction "46_46") (pintype "bidirectional"))
      (node (ref "P17") (pin "32") (pinfunction "32_32") (pintype "bidirectional"))
      (node (ref "P2") (pin "46") (pinfunction "46_46") (pintype "bidirectional"))
      (node (ref "P3") (pin "46") (pinfunction "46_46") (pintype "bidirectional"))
      (node (ref "P4") (pin "46") (pinfunction "46_46") (pintype "bidirectional"))
      (node (ref "P5") (pin "46") (pinfunction "46_46") (pintype "bidirectional"))
    )
    (net (code "50") (name "/BL0_D4") (class "Default")
      (node (ref "P1") (pin "45") (pinfunction "45_45") (pintype "bidirectional"))
      (node (ref "P17") (pin "68") (pinfunction "68_68") (pintype "bidirectional"))
      (node (ref "P2") (pin "45") (pinfunction "45_45") (pintype "bidirectional"))
      (node (ref "P3") (pin "45") (pinfunction "45_45") (pintype "bidirectional"))
      (node (ref "P4") (pin "45") (pinfunction "45_45") (pintype "bidirectional"))
      (node (ref "P5") (pin "45") (pinfunction "45_45") (pintype "bidirectional"))
    )
    (net (code "51") (name "/BL0_D5") (class "Default")
      (node (ref "P1") (pin "44") (pinfunction "44_44") (pintype "bidirectional"))
      (node (ref "P17") (pin "33") (pinfunction "33_33") (pintype "bidirectional"))
      (node (ref "P2") (pin "44") (pinfunction "44_44") (pintype "bidirectional"))
      (node (ref "P3") (pin "44") (pinfunction "44_44") (pintype "bidirectional"))
      (node (ref "P4") (pin "44") (pinfunction "44_44") (pintype "bidirectional"))
      (node (ref "P5") (pin "44") (pinfunction "44_44") (pintype "bidirectional"))
    )
    (net (code "52") (name "/BL0_D6") (class "Default")
      (node (ref "P1") (pin "43") (pinfunction "43_43") (pintype "bidirectional"))
      (node (ref "P17") (pin "69") (pinfunction "69_69") (pintype "bidirectional"))
      (node (ref "P2") (pin "43") (pinfunction "43_43") (pintype "bidirectional"))
      (node (ref "P3") (pin "43") (pinfunction "43_43") (pintype "bidirectional"))
      (node (ref "P4") (pin "43") (pinfunction "43_43") (pintype "bidirectional"))
      (node (ref "P5") (pin "43") (pinfunction "43_43") (pintype "bidirectional"))
    )
    (net (code "53") (name "/BL0_D7") (class "Default")
      (node (ref "P1") (pin "42") (pinfunction "42_42") (pintype "bidirectional"))
      (node (ref "P17") (pin "34") (pinfunction "34_34") (pintype "bidirectional"))
      (node (ref "P2") (pin "42") (pinfunction "42_42") (pintype "bidirectional"))
      (node (ref "P3") (pin "42") (pinfunction "42_42") (pintype "bidirectional"))
      (node (ref "P4") (pin "42") (pinfunction "42_42") (pintype "bidirectional"))
      (node (ref "P5") (pin "42") (pinfunction "42_42") (pintype "bidirectional"))
    )
    (net (code "54") (name "/BL0_PD0") (class "Default")
      (node (ref "P1") (pin "30") (pinfunction "30_30") (pintype "bidirectional"))
      (node (ref "P17") (pin "30") (pinfunction "30_30") (pintype "bidirectional"))
      (node (ref "P2") (pin "30") (pinfunction "30_30") (pintype "bidirectional"))
      (node (ref "P3") (pin "30") (pinfunction "30_30") (pintype "bidirectional"))
      (node (ref "P4") (pin "30") (pinfunction "30_30") (pintype "bidirectional"))
      (node (ref "P5") (pin "30") (pinfunction "30_30") (pintype "bidirectional"))
    )
    (net (code "55") (name "/BL0_PD1") (class "Default")
      (node (ref "P1") (pin "31") (pinfunction "31_31") (pintype "bidirectional"))
      (node (ref "P17") (pin "29") (pinfunction "29_29") (pintype "bidirectional"))
      (node (ref "P2") (pin "31") (pinfunction "31_31") (pintype "bidirectional"))
      (node (ref "P3") (pin "31") (pinfunction "31_31") (pintype "bidirectional"))
      (node (ref "P4") (pin "31") (pinfunction "31_31") (pintype "bidirectional"))
      (node (ref "P5") (pin "31") (pinfunction "31_31") (pintype "bidirectional"))
    )
    (net (code "56") (name "/BL0_PD2") (class "Default")
      (node (ref "P1") (pin "32") (pinfunction "32_32") (pintype "bidirectional"))
      (node (ref "P17") (pin "28") (pinfunction "28_28") (pintype "bidirectional"))
      (node (ref "P2") (pin "32") (pinfunction "32_32") (pintype "bidirectional"))
      (node (ref "P3") (pin "32") (pinfunction "32_32") (pintype "bidirectional"))
      (node (ref "P4") (pin "32") (pinfunction "32_32") (pintype "bidirectional"))
      (node (ref "P5") (pin "32") (pinfunction "32_32") (pintype "bidirectional"))
    )
    (net (code "57") (name "/BL0_PD3") (class "Default")
      (node (ref "P1") (pin "33") (pinfunction "33_33") (pintype "bidirectional"))
      (node (ref "P17") (pin "27") (pinfunction "27_27") (pintype "bidirectional"))
      (node (ref "P2") (pin "33") (pinfunction "33_33") (pintype "bidirectional"))
      (node (ref "P3") (pin "33") (pinfunction "33_33") (pintype "bidirectional"))
      (node (ref "P4") (pin "33") (pinfunction "33_33") (pintype "bidirectional"))
      (node (ref "P5") (pin "33") (pinfunction "33_33") (pintype "bidirectional"))
    )
    (net (code "58") (name "/BL0_PD4") (class "Default")
      (node (ref "P1") (pin "69") (pinfunction "69_69") (pintype "bidirectional"))
      (node (ref "P17") (pin "62") (pinfunction "62_62") (pintype "bidirectional"))
      (node (ref "P2") (pin "69") (pinfunction "69_69") (pintype "bidirectional"))
      (node (ref "P3") (pin "69") (pinfunction "69_69") (pintype "bidirectional"))
      (node (ref "P4") (pin "69") (pinfunction "69_69") (pintype "bidirectional"))
      (node (ref "P5") (pin "69") (pinfunction "69_69") (pintype "bidirectional"))
    )
    (net (code "59") (name "/BL0_PD5") (class "Default")
      (node (ref "P1") (pin "68") (pinfunction "68_68") (pintype "bidirectional"))
      (node (ref "P17") (pin "63") (pinfunction "63_63") (pintype "bidirectional"))
      (node (ref "P2") (pin "68") (pinfunction "68_68") (pintype "bidirectional"))
      (node (ref "P3") (pin "68") (pinfunction "68_68") (pintype "bidirectional"))
      (node (ref "P4") (pin "68") (pinfunction "68_68") (pintype "bidirectional"))
      (node (ref "P5") (pin "68") (pinfunction "68_68") (pintype "bidirectional"))
    )
    (net (code "60") (name "/BL0_PD6") (class "Default")
      (node (ref "P1") (pin "67") (pinfunction "67_67") (pintype "bidirectional"))
      (node (ref "P17") (pin "64") (pinfunction "64_64") (pintype "bidirectional"))
      (node (ref "P2") (pin "67") (pinfunction "67_67") (pintype "bidirectional"))
      (node (ref "P3") (pin "67") (pinfunction "67_67") (pintype "bidirectional"))
      (node (ref "P4") (pin "67") (pinfunction "67_67") (pintype "bidirectional"))
      (node (ref "P5") (pin "67") (pinfunction "67_67") (pintype "bidirectional"))
    )
    (net (code "61") (name "/BL0_PD7") (class "Default")
      (node (ref "P1") (pin "66") (pinfunction "66_66") (pintype "bidirectional"))
      (node (ref "P17") (pin "65") (pinfunction "65_65") (pintype "bidirectional"))
      (node (ref "P2") (pin "66") (pinfunction "66_66") (pintype "bidirectional"))
      (node (ref "P3") (pin "66") (pinfunction "66_66") (pintype "bidirectional"))
      (node (ref "P4") (pin "66") (pinfunction "66_66") (pintype "bidirectional"))
      (node (ref "P5") (pin "66") (pinfunction "66_66") (pintype "bidirectional"))
    )
    (net (code "62") (name "/BL1_D0") (class "Default")
      (node (ref "P10") (pin "49") (pinfunction "49_49") (pintype "bidirectional"))
      (node (ref "P17") (pin "58") (pinfunction "58_58") (pintype "bidirectional"))
      (node (ref "P6") (pin "49") (pinfunction "49_49") (pintype "bidirectional"))
      (node (ref "P7") (pin "49") (pinfunction "49_49") (pintype "bidirectional"))
      (node (ref "P8") (pin "49") (pinfunction "49_49") (pintype "bidirectional"))
      (node (ref "P9") (pin "49") (pinfunction "49_49") (pintype "bidirectional"))
    )
    (net (code "63") (name "/BL1_D1") (class "Default")
      (node (ref "P10") (pin "48") (pinfunction "48_48") (pintype "bidirectional"))
      (node (ref "P17") (pin "23") (pinfunction "23_23") (pintype "bidirectional"))
      (node (ref "P6") (pin "48") (pinfunction "48_48") (pintype "bidirectional"))
      (node (ref "P7") (pin "48") (pinfunction "48_48") (pintype "bidirectional"))
      (node (ref "P8") (pin "48") (pinfunction "48_48") (pintype "bidirectional"))
      (node (ref "P9") (pin "48") (pinfunction "48_48") (pintype "bidirectional"))
    )
    (net (code "64") (name "/BL1_D2") (class "Default")
      (node (ref "P10") (pin "47") (pinfunction "47_47") (pintype "bidirectional"))
      (node (ref "P17") (pin "59") (pinfunction "59_59") (pintype "bidirectional"))
      (node (ref "P6") (pin "47") (pinfunction "47_47") (pintype "bidirectional"))
      (node (ref "P7") (pin "47") (pinfunction "47_47") (pintype "bidirectional"))
      (node (ref "P8") (pin "47") (pinfunction "47_47") (pintype "bidirectional"))
      (node (ref "P9") (pin "47") (pinfunction "47_47") (pintype "bidirectional"))
    )
    (net (code "65") (name "/BL1_D3") (class "Default")
      (node (ref "P10") (pin "46") (pinfunction "46_46") (pintype "bidirectional"))
      (node (ref "P17") (pin "24") (pinfunction "24_24") (pintype "bidirectional"))
      (node (ref "P6") (pin "46") (pinfunction "46_46") (pintype "bidirectional"))
      (node (ref "P7") (pin "46") (pinfunction "46_46") (pintype "bidirectional"))
      (node (ref "P8") (pin "46") (pinfunction "46_46") (pintype "bidirectional"))
      (node (ref "P9") (pin "46") (pinfunction "46_46") (pintype "bidirectional"))
    )
    (net (code "66") (name "/BL1_D4") (class "Default")
      (node (ref "P10") (pin "45") (pinfunction "45_45") (pintype "bidirectional"))
      (node (ref "P17") (pin "60") (pinfunction "60_60") (pintype "bidirectional"))
      (node (ref "P6") (pin "45") (pinfunction "45_45") (pintype "bidirectional"))
      (node (ref "P7") (pin "45") (pinfunction "45_45") (pintype "bidirectional"))
      (node (ref "P8") (pin "45") (pinfunction "45_45") (pintype "bidirectional"))
      (node (ref "P9") (pin "45") (pinfunction "45_45") (pintype "bidirectional"))
    )
    (net (code "67") (name "/BL1_D5") (class "Default")
      (node (ref "P10") (pin "44") (pinfunction "44_44") (pintype "bidirectional"))
      (node (ref "P17") (pin "25") (pinfunction "25_25") (pintype "bidirectional"))
      (node (ref "P6") (pin "44") (pinfunction "44_44") (pintype "bidirectional"))
      (node (ref "P7") (pin "44") (pinfunction "44_44") (pintype "bidirectional"))
      (node (ref "P8") (pin "44") (pinfunction "44_44") (pintype "bidirectional"))
      (node (ref "P9") (pin "44") (pinfunction "44_44") (pintype "bidirectional"))
    )
    (net (code "68") (name "/BL1_D6") (class "Default")
      (node (ref "P10") (pin "43") (pinfunction "43_43") (pintype "bidirectional"))
      (node (ref "P17") (pin "61") (pinfunction "61_61") (pintype "bidirectional"))
      (node (ref "P6") (pin "43") (pinfunction "43_43") (pintype "bidirectional"))
      (node (ref "P7") (pin "43") (pinfunction "43_43") (pintype "bidirectional"))
      (node (ref "P8") (pin "43") (pinfunction "43_43") (pintype "bidirectional"))
      (node (ref "P9") (pin "43") (pinfunction "43_43") (pintype "bidirectional"))
    )
    (net (code "69") (name "/BL1_D7") (class "Default")
      (node (ref "P10") (pin "42") (pinfunction "42_42") (pintype "bidirectional"))
      (node (ref "P17") (pin "26") (pinfunction "26_26") (pintype "bidirectional"))
      (node (ref "P6") (pin "42") (pinfunction "42_42") (pintype "bidirectional"))
      (node (ref "P7") (pin "42") (pinfunction "42_42") (pintype "bidirectional"))
      (node (ref "P8") (pin "42") (pinfunction "42_42") (pintype "bidirectional"))
      (node (ref "P9") (pin "42") (pinfunction "42_42") (pintype "bidirectional"))
    )
    (net (code "70") (name "/BL1_PD0") (class "Default")
      (node (ref "P10") (pin "30") (pinfunction "30_30") (pintype "bidirectional"))
      (node (ref "P17") (pin "22") (pinfunction "22_22") (pintype "bidirectional"))
      (node (ref "P6") (pin "30") (pinfunction "30_30") (pintype "bidirectional"))
      (node (ref "P7") (pin "30") (pinfunction "30_30") (pintype "bidirectional"))
      (node (ref "P8") (pin "30") (pinfunction "30_30") (pintype "bidirectional"))
      (node (ref "P9") (pin "30") (pinfunction "30_30") (pintype "bidirectional"))
    )
    (net (code "71") (name "/BL1_PD1") (class "Default")
      (node (ref "P10") (pin "31") (pinfunction "31_31") (pintype "bidirectional"))
      (node (ref "P17") (pin "21") (pinfunction "21_21") (pintype "bidirectional"))
      (node (ref "P6") (pin "31") (pinfunction "31_31") (pintype "bidirectional"))
      (node (ref "P7") (pin "31") (pinfunction "31_31") (pintype "bidirectional"))
      (node (ref "P8") (pin "31") (pinfunction "31_31") (pintype "bidirectional"))
      (node (ref "P9") (pin "31") (pinfunction "31_31") (pintype "bidirectional"))
    )
    (net (code "72") (name "/BL1_PD2") (class "Default")
      (node (ref "P10") (pin "32") (pinfunction "32_32") (pintype "bidirectional"))
      (node (ref "P17") (pin "20") (pinfunction "20_20") (pintype "bidirectional"))
      (node (ref "P6") (pin "32") (pinfunction "32_32") (pintype "bidirectional"))
      (node (ref "P7") (pin "32") (pinfunction "32_32") (pintype "bidirectional"))
      (node (ref "P8") (pin "32") (pinfunction "32_32") (pintype "bidirectional"))
      (node (ref "P9") (pin "32") (pinfunction "32_32") (pintype "bidirectional"))
    )
    (net (code "73") (name "/BL1_PD3") (class "Default")
      (node (ref "P10") (pin "33") (pinfunction "33_33") (pintype "bidirectional"))
      (node (ref "P17") (pin "19") (pinfunction "19_19") (pintype "bidirectional"))
      (node (ref "P6") (pin "33") (pinfunction "33_33") (pintype "bidirectional"))
      (node (ref "P7") (pin "33") (pinfunction "33_33") (pintype "bidirectional"))
      (node (ref "P8") (pin "33") (pinfunction "33_33") (pintype "bidirectional"))
      (node (ref "P9") (pin "33") (pinfunction "33_33") (pintype "bidirectional"))
    )
    (net (code "74") (name "/BL1_PD4") (class "Default")
      (node (ref "P10") (pin "69") (pinfunction "69_69") (pintype "bidirectional"))
      (node (ref "P17") (pin "54") (pinfunction "54_54") (pintype "bidirectional"))
      (node (ref "P6") (pin "69") (pinfunction "69_69") (pintype "bidirectional"))
      (node (ref "P7") (pin "69") (pinfunction "69_69") (pintype "bidirectional"))
      (node (ref "P8") (pin "69") (pinfunction "69_69") (pintype "bidirectional"))
      (node (ref "P9") (pin "69") (pinfunction "69_69") (pintype "bidirectional"))
    )
    (net (code "75") (name "/BL1_PD5") (class "Default")
      (node (ref "P10") (pin "68") (pinfunction "68_68") (pintype "bidirectional"))
      (node (ref "P17") (pin "55") (pinfunction "55_55") (pintype "bidirectional"))
      (node (ref "P6") (pin "68") (pinfunction "68_68") (pintype "bidirectional"))
      (node (ref "P7") (pin "68") (pinfunction "68_68") (pintype "bidirectional"))
      (node (ref "P8") (pin "68") (pinfunction "68_68") (pintype "bidirectional"))
      (node (ref "P9") (pin "68") (pinfunction "68_68") (pintype "bidirectional"))
    )
    (net (code "76") (name "/BL1_PD6") (class "Default")
      (node (ref "P10") (pin "67") (pinfunction "67_67") (pintype "bidirectional"))
      (node (ref "P17") (pin "56") (pinfunction "56_56") (pintype "bidirectional"))
      (node (ref "P6") (pin "67") (pinfunction "67_67") (pintype "bidirectional"))
      (node (ref "P7") (pin "67") (pinfunction "67_67") (pintype "bidirectional"))
      (node (ref "P8") (pin "67") (pinfunction "67_67") (pintype "bidirectional"))
      (node (ref "P9") (pin "67") (pinfunction "67_67") (pintype "bidirectional"))
    )
    (net (code "77") (name "/BL1_PD7") (class "Default")
      (node (ref "P10") (pin "66") (pinfunction "66_66") (pintype "bidirectional"))
      (node (ref "P17") (pin "57") (pinfunction "57_57") (pintype "bidirectional"))
      (node (ref "P6") (pin "66") (pinfunction "66_66") (pintype "bidirectional"))
      (node (ref "P7") (pin "66") (pinfunction "66_66") (pintype "bidirectional"))
      (node (ref "P8") (pin "66") (pinfunction "66_66") (pintype "bidirectional"))
      (node (ref "P9") (pin "66") (pinfunction "66_66") (pintype "bidirectional"))
    )
    (net (code "78") (name "/BL2_D0") (class "Default")
      (node (ref "P11") (pin "49") (pinfunction "49_49") (pintype "bidirectional"))
      (node (ref "P12") (pin "49") (pinfunction "49_49") (pintype "bidirectional"))
      (node (ref "P13") (pin "49") (pinfunction "49_49") (pintype "bidirectional"))
      (node (ref "P14") (pin "49") (pinfunction "49_49") (pintype "bidirectional"))
      (node (ref "P15") (pin "49") (pinfunction "49_49") (pintype "bidirectional"))
      (node (ref "P17") (pin "50") (pinfunction "50_50") (pintype "bidirectional"))
    )
    (net (code "79") (name "/BL2_D1") (class "Default")
      (node (ref "P11") (pin "48") (pinfunction "48_48") (pintype "bidirectional"))
      (node (ref "P12") (pin "48") (pinfunction "48_48") (pintype "bidirectional"))
      (node (ref "P13") (pin "48") (pinfunction "48_48") (pintype "bidirectional"))
      (node (ref "P14") (pin "48") (pinfunction "48_48") (pintype "bidirectional"))
      (node (ref "P15") (pin "48") (pinfunction "48_48") (pintype "bidirectional"))
      (node (ref "P17") (pin "15") (pinfunction "15_15") (pintype "bidirectional"))
    )
    (net (code "80") (name "/BL2_D2") (class "Default")
      (node (ref "P11") (pin "47") (pinfunction "47_47") (pintype "bidirectional"))
      (node (ref "P12") (pin "47") (pinfunction "47_47") (pintype "bidirectional"))
      (node (ref "P13") (pin "47") (pinfunction "47_47") (pintype "bidirectional"))
      (node (ref "P14") (pin "47") (pinfunction "47_47") (pintype "bidirectional"))
      (node (ref "P15") (pin "47") (pinfunction "47_47") (pintype "bidirectional"))
      (node (ref "P17") (pin "51") (pinfunction "51_51") (pintype "bidirectional"))
    )
    (net (code "81") (name "/BL2_D3") (class "Default")
      (node (ref "P11") (pin "46") (pinfunction "46_46") (pintype "bidirectional"))
      (node (ref "P12") (pin "46") (pinfunction "46_46") (pintype "bidirectional"))
      (node (ref "P13") (pin "46") (pinfunction "46_46") (pintype "bidirectional"))
      (node (ref "P14") (pin "46") (pinfunction "46_46") (pintype "bidirectional"))
      (node (ref "P15") (pin "46") (pinfunction "46_46") (pintype "bidirectional"))
      (node (ref "P17") (pin "16") (pinfunction "16_16") (pintype "bidirectional"))
    )
    (net (code "82") (name "/BL2_D4") (class "Default")
      (node (ref "P11") (pin "45") (pinfunction "45_45") (pintype "bidirectional"))
      (node (ref "P12") (pin "45") (pinfunction "45_45") (pintype "bidirectional"))
      (node (ref "P13") (pin "45") (pinfunction "45_45") (pintype "bidirectional"))
      (node (ref "P14") (pin "45") (pinfunction "45_45") (pintype "bidirectional"))
      (node (ref "P15") (pin "45") (pinfunction "45_45") (pintype "bidirectional"))
      (node (ref "P17") (pin "52") (pinfunction "52_52") (pintype "bidirectional"))
    )
    (net (code "83") (name "/BL2_D5") (class "Default")
      (node (ref "P11") (pin "44") (pinfunction "44_44") (pintype "bidirectional"))
      (node (ref "P12") (pin "44") (pinfunction "44_44") (pintype "bidirectional"))
      (node (ref "P13") (pin "44") (pinfunction "44_44") (pintype "bidirectional"))
      (node (ref "P14") (pin "44") (pinfunction "44_44") (pintype "bidirectional"))
      (node (ref "P15") (pin "44") (pinfunction "44_44") (pintype "bidirectional"))
      (node (ref "P17") (pin "17") (pinfunction "17_17") (pintype "bidirectional"))
    )
    (net (code "84") (name "/BL2_D6") (class "Default")
      (node (ref "P11") (pin "43") (pinfunction "43_43") (pintype "bidirectional"))
      (node (ref "P12") (pin "43") (pinfunction "43_43") (pintype "bidirectional"))
      (node (ref "P13") (pin "43") (pinfunction "43_43") (pintype "bidirectional"))
      (node (ref "P14") (pin "43") (pinfunction "43_43") (pintype "bidirectional"))
      (node (ref "P15") (pin "43") (pinfunction "43_43") (pintype "bidirectional"))
      (node (ref "P17") (pin "53") (pinfunction "53_53") (pintype "bidirectional"))
    )
    (net (code "85") (name "/BL2_D7") (class "Default")
      (node (ref "P11") (pin "42") (pinfunction "42_42") (pintype "bidirectional"))
      (node (ref "P12") (pin "42") (pinfunction "42_42") (pintype "bidirectional"))
      (node (ref "P13") (pin "42") (pinfunction "42_42") (pintype "bidirectional"))
      (node (ref "P14") (pin "42") (pinfunction "42_42") (pintype "bidirectional"))
      (node (ref "P15") (pin "42") (pinfunction "42_42") (pintype "bidirectional"))
      (node (ref "P17") (pin "18") (pinfunction "18_18") (pintype "bidirectional"))
    )
    (net (code "86") (name "/BL2_PD0") (class "Default")
      (node (ref "P11") (pin "30") (pinfunction "30_30") (pintype "bidirectional"))
      (node (ref "P12") (pin "30") (pinfunction "30_30") (pintype "bidirectional"))
      (node (ref "P13") (pin "30") (pinfunction "30_30") (pintype "bidirectional"))
      (node (ref "P14") (pin "30") (pinfunction "30_30") (pintype "bidirectional"))
      (node (ref "P15") (pin "30") (pinfunction "30_30") (pintype "bidirectional"))
      (node (ref "P17") (pin "14") (pinfunction "14_14") (pintype "bidirectional"))
    )
    (net (code "87") (name "/BL2_PD1") (class "Default")
      (node (ref "P11") (pin "31") (pinfunction "31_31") (pintype "bidirectional"))
      (node (ref "P12") (pin "31") (pinfunction "31_31") (pintype "bidirectional"))
      (node (ref "P13") (pin "31") (pinfunction "31_31") (pintype "bidirectional"))
      (node (ref "P14") (pin "31") (pinfunction "31_31") (pintype "bidirectional"))
      (node (ref "P15") (pin "31") (pinfunction "31_31") (pintype "bidirectional"))
      (node (ref "P17") (pin "13") (pinfunction "13_13") (pintype "bidirectional"))
    )
    (net (code "88") (name "/BL2_PD2") (class "Default")
      (node (ref "P11") (pin "32") (pinfunction "32_32") (pintype "bidirectional"))
      (node (ref "P12") (pin "32") (pinfunction "32_32") (pintype "bidirectional"))
      (node (ref "P13") (pin "32") (pinfunction "32_32") (pintype "bidirectional"))
      (node (ref "P14") (pin "32") (pinfunction "32_32") (pintype "bidirectional"))
      (node (ref "P15") (pin "32") (pinfunction "32_32") (pintype "bidirectional"))
      (node (ref "P17") (pin "12") (pinfunction "12_12") (pintype "bidirectional"))
    )
    (net (code "89") (name "/BL2_PD3") (class "Default")
      (node (ref "P11") (pin "33") (pinfunction "33_33") (pintype "bidirectional"))
      (node (ref "P12") (pin "33") (pinfunction "33_33") (pintype "bidirectional"))
      (node (ref "P13") (pin "33") (pinfunction "33_33") (pintype "bidirectional"))
      (node (ref "P14") (pin "33") (pinfunction "33_33") (pintype "bidirectional"))
      (node (ref "P15") (pin "33") (pinfunction "33_33") (pintype "bidirectional"))
      (node (ref "P17") (pin "11") (pinfunction "11_11") (pintype "bidirectional"))
    )
    (net (code "90") (name "/BL2_PD4") (class "Default")
      (node (ref "P11") (pin "69") (pinfunction "69_69") (pintype "bidirectional"))
      (node (ref "P12") (pin "69") (pinfunction "69_69") (pintype "bidirectional"))
      (node (ref "P13") (pin "69") (pinfunction "69_69") (pintype "bidirectional"))
      (node (ref "P14") (pin "69") (pinfunction "69_69") (pintype "bidirectional"))
      (node (ref "P15") (pin "69") (pinfunction "69_69") (pintype "bidirectional"))
      (node (ref "P17") (pin "46") (pinfunction "46_46") (pintype "bidirectional"))
    )
    (net (code "91") (name "/BL2_PD5") (class "Default")
      (node (ref "P11") (pin "68") (pinfunction "68_68") (pintype "bidirectional"))
      (node (ref "P12") (pin "68") (pinfunction "68_68") (pintype "bidirectional"))
      (node (ref "P13") (pin "68") (pinfunction "68_68") (pintype "bidirectional"))
      (node (ref "P14") (pin "68") (pinfunction "68_68") (pintype "bidirectional"))
      (node (ref "P15") (pin "68") (pinfunction "68_68") (pintype "bidirectional"))
      (node (ref "P17") (pin "47") (pinfunction "47_47") (pintype "bidirectional"))
    )
    (net (code "92") (name "/BL2_PD6") (class "Default")
      (node (ref "P11") (pin "67") (pinfunction "67_67") (pintype "bidirectional"))
      (node (ref "P12") (pin "67") (pinfunction "67_67") (pintype "bidirectional"))
      (node (ref "P13") (pin "67") (pinfunction "67_67") (pintype "bidirectional"))
      (node (ref "P14") (pin "67") (pinfunction "67_67") (pintype "bidirectional"))
      (node (ref "P15") (pin "67") (pinfunction "67_67") (pintype "bidirectional"))
      (node (ref "P17") (pin "48") (pinfunction "48_48") (pintype "bidirectional"))
    )
    (net (code "93") (name "/BL2_PD7") (class "Default")
      (node (ref "P11") (pin "66") (pinfunction "66_66") (pintype "bidirectional"))
      (node (ref "P12") (pin "66") (pinfunction "66_66") (pintype "bidirectional"))
      (node (ref "P13") (pin "66") (pinfunction "66_66") (pintype "bidirectional"))
      (node (ref "P14") (pin "66") (pinfunction "66_66") (pintype "bidirectional"))
      (node (ref "P15") (pin "66") (pinfunction "66_66") (pintype "bidirectional"))
      (node (ref "P17") (pin "49") (pinfunction "49_49") (pintype "bidirectional"))
    )
    (net (code "94") (name "/CIRAM_1") (class "Default")
      (node (ref "J1") (pin "3") (pinfunction "3_3") (pintype "passive"))
      (node (ref "P1") (pin "57") (pinfunction "57_57") (pintype "bidirectional"))
    )
    (net (code "95") (name "/CIRAM_2") (class "Default")
      (node (ref "J1") (pin "8") (pinfunction "8_8") (pintype "passive"))
      (node (ref "P2") (pin "57") (pinfunction "57_57") (pintype "bidirectional"))
    )
    (net (code "96") (name "/CIRAM_3") (class "Default")
      (node (ref "J1") (pin "13") (pinfunction "13_13") (pintype "passive"))
      (node (ref "P3") (pin "57") (pinfunction "57_57") (pintype "bidirectional"))
    )
    (net (code "97") (name "/CIRAM_4") (class "Default")
      (node (ref "J1") (pin "18") (pinfunction "18_18") (pintype "passive"))
      (node (ref "P4") (pin "57") (pinfunction "57_57") (pintype "bidirectional"))
    )
    (net (code "98") (name "/CIRAM_5") (class "Default")
      (node (ref "J1") (pin "23") (pinfunction "23_23") (pintype "passive"))
      (node (ref "P5") (pin "57") (pinfunction "57_57") (pintype "bidirectional"))
    )
    (net (code "99") (name "/CIRAM_6") (class "Default")
      (node (ref "J2") (pin "3") (pinfunction "3_3") (pintype "passive"))
      (node (ref "P6") (pin "57") (pinfunction "57_57") (pintype "bidirectional"))
    )
    (net (code "100") (name "/CIRAM_7") (class "Default")
      (node (ref "J2") (pin "8") (pinfunction "8_8") (pintype "passive"))
      (node (ref "P7") (pin "57") (pinfunction "57_57") (pintype "bidirectional"))
    )
    (net (code "101") (name "/CIRAM_8") (class "Default")
      (node (ref "J2") (pin "13") (pinfunction "13_13") (pintype "passive"))
      (node (ref "P8") (pin "57") (pinfunction "57_57") (pintype "bidirectional"))
    )
    (net (code "102") (name "/CIRAM_9") (class "Default")
      (node (ref "J2") (pin "18") (pinfunction "18_18") (pintype "passive"))
      (node (ref "P9") (pin "57") (pinfunction "57_57") (pintype "bidirectional"))
    )
    (net (code "103") (name "/CIRAM_10") (class "Default")
      (node (ref "J2") (pin "23") (pinfunction "23_23") (pintype "passive"))
      (node (ref "P10") (pin "57") (pinfunction "57_57") (pintype "bidirectional"))
    )
    (net (code "104") (name "/CIRAM_11") (class "Default")
      (node (ref "J3") (pin "3") (pinfunction "3_3") (pintype "passive"))
      (node (ref "P11") (pin "57") (pinfunction "57_57") (pintype "bidirectional"))
    )
    (net (code "105") (name "/CIRAM_12") (class "Default")
      (node (ref "J3") (pin "8") (pinfunction "8_8") (pintype "passive"))
      (node (ref "P12") (pin "57") (pinfunction "57_57") (pintype "bidirectional"))
    )
    (net (code "106") (name "/CIRAM_13") (class "Default")
      (node (ref "J3") (pin "13") (pinfunction "13_13") (pintype "passive"))
      (node (ref "P13") (pin "57") (pinfunction "57_57") (pintype "bidirectional"))
    )
    (net (code "107") (name "/CIRAM_14") (class "Default")
      (node (ref "J3") (pin "18") (pinfunction "18_18") (pintype "passive"))
      (node (ref "P14") (pin "57") (pinfunction "57_57") (pintype "bidirectional"))
    )
    (net (code "108") (name "/CIRAM_15") (class "Default")
      (node (ref "J3") (pin "23") (pinfunction "23_23") (pintype "passive"))
      (node (ref "P15") (pin "57") (pinfunction "57_57") (pintype "bidirectional"))
    )
    (net (code "109") (name "/CS_1") (class "Default")
      (node (ref "P1") (pin "65") (pinfunction "65_65") (pintype "bidirectional"))
      (node (ref "P18") (pin "52") (pinfunction "52_52") (pintype "bidirectional"))
    )
    (net (code "110") (name "/CS_2") (class "Default")
      (node (ref "P18") (pin "51") (pinfunction "51_51") (pintype "bidirectional"))
      (node (ref "P2") (pin "65") (pinfunction "65_65") (pintype "bidirectional"))
    )
    (net (code "111") (name "/CS_3") (class "Default")
      (node (ref "P18") (pin "50") (pinfunction "50_50") (pintype "bidirectional"))
      (node (ref "P3") (pin "65") (pinfunction "65_65") (pintype "bidirectional"))
    )
    (net (code "112") (name "/CS_4") (class "Default")
      (node (ref "P18") (pin "49") (pinfunction "49_49") (pintype "bidirectional"))
      (node (ref "P4") (pin "65") (pinfunction "65_65") (pintype "bidirectional"))
    )
    (net (code "113") (name "/CS_5") (class "Default")
      (node (ref "P18") (pin "48") (pinfunction "48_48") (pintype "bidirectional"))
      (node (ref "P5") (pin "65") (pinfunction "65_65") (pintype "bidirectional"))
    )
    (net (code "114") (name "/CS_6") (class "Default")
      (node (ref "P18") (pin "47") (pinfunction "47_47") (pintype "bidirectional"))
      (node (ref "P6") (pin "65") (pinfunction "65_65") (pintype "bidirectional"))
    )
    (net (code "115") (name "/CS_7") (class "Default")
      (node (ref "P18") (pin "46") (pinfunction "46_46") (pintype "bidirectional"))
      (node (ref "P7") (pin "65") (pinfunction "65_65") (pintype "bidirectional"))
    )
    (net (code "116") (name "/CS_8") (class "Default")
      (node (ref "P18") (pin "45") (pinfunction "45_45") (pintype "bidirectional"))
      (node (ref "P8") (pin "65") (pinfunction "65_65") (pintype "bidirectional"))
    )
    (net (code "117") (name "/CS_9") (class "Default")
      (node (ref "P18") (pin "44") (pinfunction "44_44") (pintype "bidirectional"))
      (node (ref "P9") (pin "65") (pinfunction "65_65") (pintype "bidirectional"))
    )
    (net (code "118") (name "/CS_10") (class "Default")
      (node (ref "P10") (pin "65") (pinfunction "65_65") (pintype "bidirectional"))
      (node (ref "P18") (pin "43") (pinfunction "43_43") (pintype "bidirectional"))
    )
    (net (code "119") (name "/CS_11") (class "Default")
      (node (ref "P11") (pin "65") (pinfunction "65_65") (pintype "bidirectional"))
      (node (ref "P18") (pin "42") (pinfunction "42_42") (pintype "bidirectional"))
    )
    (net (code "120") (name "/CS_12") (class "Default")
      (node (ref "P12") (pin "65") (pinfunction "65_65") (pintype "bidirectional"))
      (node (ref "P18") (pin "41") (pinfunction "41_41") (pintype "bidirectional"))
    )
    (net (code "121") (name "/CS_13") (class "Default")
      (node (ref "P13") (pin "65") (pinfunction "65_65") (pintype "bidirectional"))
      (node (ref "P18") (pin "40") (pinfunction "40_40") (pintype "bidirectional"))
    )
    (net (code "122") (name "/CS_14") (class "Default")
      (node (ref "P14") (pin "65") (pinfunction "65_65") (pintype "bidirectional"))
      (node (ref "P18") (pin "39") (pinfunction "39_39") (pintype "bidirectional"))
    )
    (net (code "123") (name "/CS_15") (class "Default")
      (node (ref "P15") (pin "65") (pinfunction "65_65") (pintype "bidirectional"))
      (node (ref "P18") (pin "38") (pinfunction "38_38") (pintype "bidirectional"))
    )
    (net (code "124") (name "/HV_1") (class "Default")
      (node (ref "P1") (pin "22") (pinfunction "22_22") (pintype "bidirectional"))
      (node (ref "P17") (pin "10") (pinfunction "10_10") (pintype "bidirectional"))
    )
    (net (code "125") (name "/HV_2") (class "Default")
      (node (ref "P17") (pin "45") (pinfunction "45_45") (pintype "bidirectional"))
      (node (ref "P2") (pin "22") (pinfunction "22_22") (pintype "bidirectional"))
    )
    (net (code "126") (name "/HV_3") (class "Default")
      (node (ref "P17") (pin "9") (pinfunction "9_9") (pintype "bidirectional"))
      (node (ref "P3") (pin "22") (pinfunction "22_22") (pintype "bidirectional"))
    )
    (net (code "127") (name "/HV_4") (class "Default")
      (node (ref "P17") (pin "44") (pinfunction "44_44") (pintype "bidirectional"))
      (node (ref "P4") (pin "22") (pinfunction "22_22") (pintype "bidirectional"))
    )
    (net (code "128") (name "/HV_5") (class "Default")
      (node (ref "P17") (pin "8") (pinfunction "8_8") (pintype "bidirectional"))
      (node (ref "P5") (pin "22") (pinfunction "22_22") (pintype "bidirectional"))
    )
    (net (code "129") (name "/HV_6") (class "Default")
      (node (ref "P17") (pin "43") (pinfunction "43_43") (pintype "bidirectional"))
      (node (ref "P6") (pin "22") (pinfunction "22_22") (pintype "bidirectional"))
    )
    (net (code "130") (name "/HV_7") (class "Default")
      (node (ref "P17") (pin "7") (pinfunction "7_7") (pintype "bidirectional"))
      (node (ref "P7") (pin "22") (pinfunction "22_22") (pintype "bidirectional"))
    )
    (net (code "131") (name "/HV_8") (class "Default")
      (node (ref "P17") (pin "42") (pinfunction "42_42") (pintype "bidirectional"))
      (node (ref "P8") (pin "22") (pinfunction "22_22") (pintype "bidirectional"))
    )
    (net (code "132") (name "/HV_9") (class "Default")
      (node (ref "P17") (pin "6") (pinfunction "6_6") (pintype "bidirectional"))
      (node (ref "P9") (pin "22") (pinfunction "22_22") (pintype "bidirectional"))
    )
    (net (code "133") (name "/HV_10") (class "Default")
      (node (ref "P10") (pin "22") (pinfunction "22_22") (pintype "bidirectional"))
      (node (ref "P17") (pin "41") (pinfunction "41_41") (pintype "bidirectional"))
    )
    (net (code "134") (name "/HV_11") (class "Default")
      (node (ref "P11") (pin "22") (pinfunction "22_22") (pintype "bidirectional"))
      (node (ref "P17") (pin "5") (pinfunction "5_5") (pintype "bidirectional"))
    )
    (net (code "135") (name "/HV_12") (class "Default")
      (node (ref "P12") (pin "22") (pinfunction "22_22") (pintype "bidirectional"))
      (node (ref "P17") (pin "40") (pinfunction "40_40") (pintype "bidirectional"))
    )
    (net (code "136") (name "/HV_13") (class "Default")
      (node (ref "P13") (pin "22") (pinfunction "22_22") (pintype "bidirectional"))
      (node (ref "P17") (pin "4") (pinfunction "4_4") (pintype "bidirectional"))
    )
    (net (code "137") (name "/HV_14") (class "Default")
      (node (ref "P14") (pin "22") (pinfunction "22_22") (pintype "bidirectional"))
      (node (ref "P17") (pin "39") (pinfunction "39_39") (pintype "bidirectional"))
    )
    (net (code "138") (name "/HV_15") (class "Default")
      (node (ref "P15") (pin "22") (pinfunction "22_22") (pintype "bidirectional"))
      (node (ref "P17") (pin "3") (pinfunction "3_3") (pintype "bidirectional"))
    )
    (net (code "139") (name "/IRQ_1") (class "Default")
      (node (ref "J1") (pin "2") (pinfunction "2_2") (pintype "passive"))
      (node (ref "P1") (pin "15") (pinfunction "15_15") (pintype "bidirectional"))
    )
    (net (code "140") (name "/IRQ_2") (class "Default")
      (node (ref "J1") (pin "7") (pinfunction "7_7") (pintype "passive"))
      (node (ref "P2") (pin "15") (pinfunction "15_15") (pintype "bidirectional"))
    )
    (net (code "141") (name "/IRQ_3") (class "Default")
      (node (ref "J1") (pin "12") (pinfunction "12_12") (pintype "passive"))
      (node (ref "P3") (pin "15") (pinfunction "15_15") (pintype "bidirectional"))
    )
    (net (code "142") (name "/IRQ_4") (class "Default")
      (node (ref "J1") (pin "17") (pinfunction "17_17") (pintype "passive"))
      (node (ref "P4") (pin "15") (pinfunction "15_15") (pintype "bidirectional"))
    )
    (net (code "143") (name "/IRQ_5") (class "Default")
      (node (ref "J1") (pin "22") (pinfunction "22_22") (pintype "passive"))
      (node (ref "P5") (pin "15") (pinfunction "15_15") (pintype "bidirectional"))
    )
    (net (code "144") (name "/IRQ_6") (class "Default")
      (node (ref "J2") (pin "2") (pinfunction "2_2") (pintype "passive"))
      (node (ref "P6") (pin "15") (pinfunction "15_15") (pintype "bidirectional"))
    )
    (net (code "145") (name "/IRQ_7") (class "Default")
      (node (ref "J2") (pin "7") (pinfunction "7_7") (pintype "passive"))
      (node (ref "P7") (pin "15") (pinfunction "15_15") (pintype "bidirectional"))
    )
    (net (code "146") (name "/IRQ_8") (class "Default")
      (node (ref "J2") (pin "12") (pinfunction "12_12") (pintype "passive"))
      (node (ref "P8") (pin "15") (pinfunction "15_15") (pintype "bidirectional"))
    )
    (net (code "147") (name "/IRQ_9") (class "Default")
      (node (ref "J2") (pin "17") (pinfunction "17_17") (pintype "passive"))
      (node (ref "P9") (pin "15") (pinfunction "15_15") (pintype "bidirectional"))
    )
    (net (code "148") (name "/IRQ_10") (class "Default")
      (node (ref "J2") (pin "22") (pinfunction "22_22") (pintype "passive"))
      (node (ref "P10") (pin "15") (pinfunction "15_15") (pintype "bidirectional"))
    )
    (net (code "149") (name "/IRQ_11") (class "Default")
      (node (ref "J3") (pin "2") (pinfunction "2_2") (pintype "passive"))
      (node (ref "P11") (pin "15") (pinfunction "15_15") (pintype "bidirectional"))
    )
    (net (code "150") (name "/IRQ_12") (class "Default")
      (node (ref "J3") (pin "7") (pinfunction "7_7") (pintype "passive"))
      (node (ref "P12") (pin "15") (pinfunction "15_15") (pintype "bidirectional"))
    )
    (net (code "151") (name "/IRQ_13") (class "Default")
      (node (ref "J3") (pin "12") (pinfunction "12_12") (pintype "passive"))
      (node (ref "P13") (pin "15") (pinfunction "15_15") (pintype "bidirectional"))
    )
    (net (code "152") (name "/IRQ_14") (class "Default")
      (node (ref "J3") (pin "17") (pinfunction "17_17") (pintype "passive"))
      (node (ref "P14") (pin "15") (pinfunction "15_15") (pintype "bidirectional"))
    )
    (net (code "153") (name "/IRQ_15") (class "Default")
      (node (ref "J3") (pin "22") (pinfunction "22_22") (pintype "passive"))
      (node (ref "P15") (pin "15") (pinfunction "15_15") (pintype "bidirectional"))
    )
    (net (code "154") (name "/LC0") (class "Default")
      (node (ref "P16") (pin "13") (pinfunction "13_13") (pintype "bidirectional"))
      (node (ref "P19") (pin "P$1") (pinfunction "1_P$1") (pintype "passive"))
      (node (ref "P19") (pin "P$2") (pinfunction "2_P$2") (pintype "passive"))
      (node (ref "P20") (pin "P$1") (pinfunction "1_P$1") (pintype "passive"))
    )
    (net (code "155") (name "/LC1") (class "Default")
      (node (ref "P16") (pin "14") (pinfunction "14_14") (pintype "bidirectional"))
      (node (ref "P20") (pin "P$2") (pinfunction "2_P$2") (pintype "passive"))
      (node (ref "P21") (pin "P$1") (pinfunction "1_P$1") (pintype "passive"))
      (node (ref "P21") (pin "P$2") (pinfunction "2_P$2") (pintype "passive"))
    )
    (net (code "156") (name "/LS0") (class "Default")
      (node (ref "P16") (pin "10") (pinfunction "10_10") (pintype "bidirectional"))
      (node (ref "P20") (pin "P$5") (pinfunction "5_P$5") (pintype "passive"))
    )
    (net (code "157") (name "/LS1") (class "Default")
      (node (ref "P16") (pin "11") (pinfunction "11_11") (pintype "bidirectional"))
      (node (ref "P19") (pin "P$7") (pinfunction "7_P$7") (pintype "passive"))
      (node (ref "P20") (pin "P$4") (pinfunction "4_P$4") (pintype "passive"))
    )
    (net (code "158") (name "/LS2") (class "Default")
      (node (ref "P16") (pin "12") (pinfunction "12_12") (pintype "bidirectional"))
      (node (ref "P19") (pin "P$6") (pinfunction "6_P$6") (pintype "passive"))
      (node (ref "P20") (pin "P$3") (pinfunction "3_P$3") (pintype "passive"))
    )
    (net (code "159") (name "/LS3") (class "Default")
      (node (ref "P16") (pin "3") (pinfunction "3_3") (pintype "bidirectional"))
      (node (ref "P19") (pin "P$5") (pinfunction "5_P$5") (pintype "passive"))
      (node (ref "P21") (pin "P$7") (pinfunction "7_P$7") (pintype "passive"))
    )
    (net (code "160") (name "/LS4") (class "Default")
      (node (ref "P16") (pin "4") (pinfunction "4_4") (pintype "bidirectional"))
      (node (ref "P19") (pin "P$4") (pinfunction "4_P$4") (pintype "passive"))
      (node (ref "P21") (pin "P$6") (pinfunction "6_P$6") (pintype "passive"))
    )
    (net (code "161") (name "/LS5") (class "Default")
      (node (ref "P16") (pin "5") (pinfunction "5_5") (pintype "bidirectional"))
      (node (ref "P19") (pin "P$3") (pinfunction "3_P$3") (pintype "passive"))
      (node (ref "P21") (pin "P$5") (pinfunction "5_P$5") (pintype "passive"))
    )
    (net (code "162") (name "/LS6") (class "Default")
      (node (ref "P16") (pin "6") (pinfunction "6_6") (pintype "bidirectional"))
      (node (ref "P20") (pin "P$7") (pinfunction "7_P$7") (pintype "passive"))
      (node (ref "P21") (pin "P$4") (pinfunction "4_P$4") (pintype "passive"))
    )
    (net (code "163") (name "/LS7") (class "Default")
      (node (ref "P16") (pin "7") (pinfunction "7_7") (pintype "bidirectional"))
      (node (ref "P20") (pin "P$6") (pinfunction "6_P$6") (pintype "passive"))
      (node (ref "P21") (pin "P$3") (pinfunction "3_P$3") (pintype "passive"))
    )
    (net (code "164") (name "/M2_1") (class "Default")
      (node (ref "J1") (pin "1") (pinfunction "1_1") (pintype "passive"))
      (node (ref "P1") (pin "38") (pinfunction "38_38") (pintype "bidirectional"))
    )
    (net (code "165") (name "/M2_2") (class "Default")
      (node (ref "J1") (pin "6") (pinfunction "6_6") (pintype "passive"))
      (node (ref "P2") (pin "38") (pinfunction "38_38") (pintype "bidirectional"))
    )
    (net (code "166") (name "/M2_3") (class "Default")
      (node (ref "J1") (pin "11") (pinfunction "11_11") (pintype "passive"))
      (node (ref "P3") (pin "38") (pinfunction "38_38") (pintype "bidirectional"))
    )
    (net (code "167") (name "/M2_4") (class "Default")
      (node (ref "J1") (pin "16") (pinfunction "16_16") (pintype "passive"))
      (node (ref "P4") (pin "38") (pinfunction "38_38") (pintype "bidirectional"))
    )
    (net (code "168") (name "/M2_5") (class "Default")
      (node (ref "J1") (pin "21") (pinfunction "21_21") (pintype "passive"))
      (node (ref "P5") (pin "38") (pinfunction "38_38") (pintype "bidirectional"))
    )
    (net (code "169") (name "/M2_6") (class "Default")
      (node (ref "J2") (pin "1") (pinfunction "1_1") (pintype "passive"))
      (node (ref "P6") (pin "38") (pinfunction "38_38") (pintype "bidirectional"))
    )
    (net (code "170") (name "/M2_7") (class "Default")
      (node (ref "J2") (pin "6") (pinfunction "6_6") (pintype "passive"))
      (node (ref "P7") (pin "38") (pinfunction "38_38") (pintype "bidirectional"))
    )
    (net (code "171") (name "/M2_8") (class "Default")
      (node (ref "J2") (pin "11") (pinfunction "11_11") (pintype "passive"))
      (node (ref "P8") (pin "38") (pinfunction "38_38") (pintype "bidirectional"))
    )
    (net (code "172") (name "/M2_9") (class "Default")
      (node (ref "J2") (pin "16") (pinfunction "16_16") (pintype "passive"))
      (node (ref "P9") (pin "38") (pinfunction "38_38") (pintype "bidirectional"))
    )
    (net (code "173") (name "/M2_10") (class "Default")
      (node (ref "J2") (pin "21") (pinfunction "21_21") (pintype "passive"))
      (node (ref "P10") (pin "38") (pinfunction "38_38") (pintype "bidirectional"))
    )
    (net (code "174") (name "/M2_11") (class "Default")
      (node (ref "J3") (pin "1") (pinfunction "1_1") (pintype "passive"))
      (node (ref "P11") (pin "38") (pinfunction "38_38") (pintype "bidirectional"))
    )
    (net (code "175") (name "/M2_12") (class "Default")
      (node (ref "J3") (pin "6") (pinfunction "6_6") (pintype "passive"))
      (node (ref "P12") (pin "38") (pinfunction "38_38") (pintype "bidirectional"))
    )
    (net (code "176") (name "/M2_13") (class "Default")
      (node (ref "J3") (pin "11") (pinfunction "11_11") (pintype "passive"))
      (node (ref "P13") (pin "38") (pinfunction "38_38") (pintype "bidirectional"))
    )
    (net (code "177") (name "/M2_14") (class "Default")
      (node (ref "J3") (pin "16") (pinfunction "16_16") (pintype "passive"))
      (node (ref "P14") (pin "38") (pinfunction "38_38") (pintype "bidirectional"))
    )
    (net (code "178") (name "/M2_15") (class "Default")
      (node (ref "J3") (pin "21") (pinfunction "21_21") (pintype "passive"))
      (node (ref "P15") (pin "38") (pinfunction "38_38") (pintype "bidirectional"))
    )
    (net (code "179") (name "/PA0_B1") (class "Default")
      (node (ref "P1") (pin "29") (pinfunction "29_29") (pintype "bidirectional"))
      (node (ref "P18") (pin "56") (pinfunction "56_56") (pintype "bidirectional"))
      (node (ref "P2") (pin "29") (pinfunction "29_29") (pintype "bidirectional"))
      (node (ref "P3") (pin "29") (pinfunction "29_29") (pintype "bidirectional"))
      (node (ref "P4") (pin "29") (pinfunction "29_29") (pintype "bidirectional"))
      (node (ref "P5") (pin "29") (pinfunction "29_29") (pintype "bidirectional"))
      (node (ref "P6") (pin "29") (pinfunction "29_29") (pintype "bidirectional"))
      (node (ref "P7") (pin "29") (pinfunction "29_29") (pintype "bidirectional"))
    )
    (net (code "180") (name "/PA0_B2") (class "Default")
      (node (ref "P10") (pin "29") (pinfunction "29_29") (pintype "bidirectional"))
      (node (ref "P11") (pin "29") (pinfunction "29_29") (pintype "bidirectional"))
      (node (ref "P12") (pin "29") (pinfunction "29_29") (pintype "bidirectional"))
      (node (ref "P13") (pin "29") (pinfunction "29_29") (pintype "bidirectional"))
      (node (ref "P14") (pin "29") (pinfunction "29_29") (pintype "bidirectional"))
      (node (ref "P15") (pin "29") (pinfunction "29_29") (pintype "bidirectional"))
      (node (ref "P16") (pin "20") (pinfunction "20_20") (pintype "bidirectional"))
      (node (ref "P8") (pin "29") (pinfunction "29_29") (pintype "bidirectional"))
      (node (ref "P9") (pin "29") (pinfunction "29_29") (pintype "bidirectional"))
    )
    (net (code "181") (name "/PA1_B1") (class "Default")
      (node (ref "P1") (pin "28") (pinfunction "28_28") (pintype "bidirectional"))
      (node (ref "P18") (pin "57") (pinfunction "57_57") (pintype "bidirectional"))
      (node (ref "P2") (pin "28") (pinfunction "28_28") (pintype "bidirectional"))
      (node (ref "P3") (pin "28") (pinfunction "28_28") (pintype "bidirectional"))
      (node (ref "P4") (pin "28") (pinfunction "28_28") (pintype "bidirectional"))
      (node (ref "P5") (pin "28") (pinfunction "28_28") (pintype "bidirectional"))
      (node (ref "P6") (pin "28") (pinfunction "28_28") (pintype "bidirectional"))
      (node (ref "P7") (pin "28") (pinfunction "28_28") (pintype "bidirectional"))
    )
    (net (code "182") (name "/PA1_B2") (class "Default")
      (node (ref "P10") (pin "28") (pinfunction "28_28") (pintype "bidirectional"))
      (node (ref "P11") (pin "28") (pinfunction "28_28") (pintype "bidirectional"))
      (node (ref "P12") (pin "28") (pinfunction "28_28") (pintype "bidirectional"))
      (node (ref "P13") (pin "28") (pinfunction "28_28") (pintype "bidirectional"))
      (node (ref "P14") (pin "28") (pinfunction "28_28") (pintype "bidirectional"))
      (node (ref "P15") (pin "28") (pinfunction "28_28") (pintype "bidirectional"))
      (node (ref "P16") (pin "21") (pinfunction "21_21") (pintype "bidirectional"))
      (node (ref "P8") (pin "28") (pinfunction "28_28") (pintype "bidirectional"))
      (node (ref "P9") (pin "28") (pinfunction "28_28") (pintype "bidirectional"))
    )
    (net (code "183") (name "/PA2_B1") (class "Default")
      (node (ref "P1") (pin "27") (pinfunction "27_27") (pintype "bidirectional"))
      (node (ref "P18") (pin "58") (pinfunction "58_58") (pintype "bidirectional"))
      (node (ref "P2") (pin "27") (pinfunction "27_27") (pintype "bidirectional"))
      (node (ref "P3") (pin "27") (pinfunction "27_27") (pintype "bidirectional"))
      (node (ref "P4") (pin "27") (pinfunction "27_27") (pintype "bidirectional"))
      (node (ref "P5") (pin "27") (pinfunction "27_27") (pintype "bidirectional"))
      (node (ref "P6") (pin "27") (pinfunction "27_27") (pintype "bidirectional"))
      (node (ref "P7") (pin "27") (pinfunction "27_27") (pintype "bidirectional"))
    )
    (net (code "184") (name "/PA2_B2") (class "Default")
      (node (ref "P10") (pin "27") (pinfunction "27_27") (pintype "bidirectional"))
      (node (ref "P11") (pin "27") (pinfunction "27_27") (pintype "bidirectional"))
      (node (ref "P12") (pin "27") (pinfunction "27_27") (pintype "bidirectional"))
      (node (ref "P13") (pin "27") (pinfunction "27_27") (pintype "bidirectional"))
      (node (ref "P14") (pin "27") (pinfunction "27_27") (pintype "bidirectional"))
      (node (ref "P15") (pin "27") (pinfunction "27_27") (pintype "bidirectional"))
      (node (ref "P16") (pin "22") (pinfunction "22_22") (pintype "bidirectional"))
      (node (ref "P8") (pin "27") (pinfunction "27_27") (pintype "bidirectional"))
      (node (ref "P9") (pin "27") (pinfunction "27_27") (pintype "bidirectional"))
    )
    (net (code "185") (name "/PA3_B1") (class "Default")
      (node (ref "P1") (pin "26") (pinfunction "26_26") (pintype "bidirectional"))
      (node (ref "P18") (pin "59") (pinfunction "59_59") (pintype "bidirectional"))
      (node (ref "P2") (pin "26") (pinfunction "26_26") (pintype "bidirectional"))
      (node (ref "P3") (pin "26") (pinfunction "26_26") (pintype "bidirectional"))
      (node (ref "P4") (pin "26") (pinfunction "26_26") (pintype "bidirectional"))
      (node (ref "P5") (pin "26") (pinfunction "26_26") (pintype "bidirectional"))
      (node (ref "P6") (pin "26") (pinfunction "26_26") (pintype "bidirectional"))
      (node (ref "P7") (pin "26") (pinfunction "26_26") (pintype "bidirectional"))
    )
    (net (code "186") (name "/PA3_B2") (class "Default")
      (node (ref "P10") (pin "26") (pinfunction "26_26") (pintype "bidirectional"))
      (node (ref "P11") (pin "26") (pinfunction "26_26") (pintype "bidirectional"))
      (node (ref "P12") (pin "26") (pinfunction "26_26") (pintype "bidirectional"))
      (node (ref "P13") (pin "26") (pinfunction "26_26") (pintype "bidirectional"))
      (node (ref "P14") (pin "26") (pinfunction "26_26") (pintype "bidirectional"))
      (node (ref "P15") (pin "26") (pinfunction "26_26") (pintype "bidirectional"))
      (node (ref "P16") (pin "23") (pinfunction "23_23") (pintype "bidirectional"))
      (node (ref "P8") (pin "26") (pinfunction "26_26") (pintype "bidirectional"))
      (node (ref "P9") (pin "26") (pinfunction "26_26") (pintype "bidirectional"))
    )
    (net (code "187") (name "/PA4_B1") (class "Default")
      (node (ref "P1") (pin "25") (pinfunction "25_25") (pintype "bidirectional"))
      (node (ref "P18") (pin "60") (pinfunction "60_60") (pintype "bidirectional"))
      (node (ref "P2") (pin "25") (pinfunction "25_25") (pintype "bidirectional"))
      (node (ref "P3") (pin "25") (pinfunction "25_25") (pintype "bidirectional"))
      (node (ref "P4") (pin "25") (pinfunction "25_25") (pintype "bidirectional"))
      (node (ref "P5") (pin "25") (pinfunction "25_25") (pintype "bidirectional"))
      (node (ref "P6") (pin "25") (pinfunction "25_25") (pintype "bidirectional"))
      (node (ref "P7") (pin "25") (pinfunction "25_25") (pintype "bidirectional"))
    )
    (net (code "188") (name "/PA4_B2") (class "Default")
      (node (ref "P10") (pin "25") (pinfunction "25_25") (pintype "bidirectional"))
      (node (ref "P11") (pin "25") (pinfunction "25_25") (pintype "bidirectional"))
      (node (ref "P12") (pin "25") (pinfunction "25_25") (pintype "bidirectional"))
      (node (ref "P13") (pin "25") (pinfunction "25_25") (pintype "bidirectional"))
      (node (ref "P14") (pin "25") (pinfunction "25_25") (pintype "bidirectional"))
      (node (ref "P15") (pin "25") (pinfunction "25_25") (pintype "bidirectional"))
      (node (ref "P16") (pin "24") (pinfunction "24_24") (pintype "bidirectional"))
      (node (ref "P8") (pin "25") (pinfunction "25_25") (pintype "bidirectional"))
      (node (ref "P9") (pin "25") (pinfunction "25_25") (pintype "bidirectional"))
    )
    (net (code "189") (name "/PA5_B1") (class "Default")
      (node (ref "P1") (pin "24") (pinfunction "24_24") (pintype "bidirectional"))
      (node (ref "P18") (pin "61") (pinfunction "61_61") (pintype "bidirectional"))
      (node (ref "P2") (pin "24") (pinfunction "24_24") (pintype "bidirectional"))
      (node (ref "P3") (pin "24") (pinfunction "24_24") (pintype "bidirectional"))
      (node (ref "P4") (pin "24") (pinfunction "24_24") (pintype "bidirectional"))
      (node (ref "P5") (pin "24") (pinfunction "24_24") (pintype "bidirectional"))
      (node (ref "P6") (pin "24") (pinfunction "24_24") (pintype "bidirectional"))
      (node (ref "P7") (pin "24") (pinfunction "24_24") (pintype "bidirectional"))
    )
    (net (code "190") (name "/PA5_B2") (class "Default")
      (node (ref "P10") (pin "24") (pinfunction "24_24") (pintype "bidirectional"))
      (node (ref "P11") (pin "24") (pinfunction "24_24") (pintype "bidirectional"))
      (node (ref "P12") (pin "24") (pinfunction "24_24") (pintype "bidirectional"))
      (node (ref "P13") (pin "24") (pinfunction "24_24") (pintype "bidirectional"))
      (node (ref "P14") (pin "24") (pinfunction "24_24") (pintype "bidirectional"))
      (node (ref "P15") (pin "24") (pinfunction "24_24") (pintype "bidirectional"))
      (node (ref "P16") (pin "25") (pinfunction "25_25") (pintype "bidirectional"))
      (node (ref "P8") (pin "24") (pinfunction "24_24") (pintype "bidirectional"))
      (node (ref "P9") (pin "24") (pinfunction "24_24") (pintype "bidirectional"))
    )
    (net (code "191") (name "/PA6_B1") (class "Default")
      (node (ref "P1") (pin "23") (pinfunction "23_23") (pintype "bidirectional"))
      (node (ref "P18") (pin "62") (pinfunction "62_62") (pintype "bidirectional"))
      (node (ref "P2") (pin "23") (pinfunction "23_23") (pintype "bidirectional"))
      (node (ref "P3") (pin "23") (pinfunction "23_23") (pintype "bidirectional"))
      (node (ref "P4") (pin "23") (pinfunction "23_23") (pintype "bidirectional"))
      (node (ref "P5") (pin "23") (pinfunction "23_23") (pintype "bidirectional"))
      (node (ref "P6") (pin "23") (pinfunction "23_23") (pintype "bidirectional"))
      (node (ref "P7") (pin "23") (pinfunction "23_23") (pintype "bidirectional"))
    )
    (net (code "192") (name "/PA6_B2") (class "Default")
      (node (ref "P10") (pin "23") (pinfunction "23_23") (pintype "bidirectional"))
      (node (ref "P11") (pin "23") (pinfunction "23_23") (pintype "bidirectional"))
      (node (ref "P12") (pin "23") (pinfunction "23_23") (pintype "bidirectional"))
      (node (ref "P13") (pin "23") (pinfunction "23_23") (pintype "bidirectional"))
      (node (ref "P14") (pin "23") (pinfunction "23_23") (pintype "bidirectional"))
      (node (ref "P15") (pin "23") (pinfunction "23_23") (pintype "bidirectional"))
      (node (ref "P16") (pin "26") (pinfunction "26_26") (pintype "bidirectional"))
      (node (ref "P8") (pin "23") (pinfunction "23_23") (pintype "bidirectional"))
      (node (ref "P9") (pin "23") (pinfunction "23_23") (pintype "bidirectional"))
    )
    (net (code "193") (name "/PA7_B1") (class "Default")
      (node (ref "P1") (pin "59") (pinfunction "59_59") (pintype "bidirectional"))
      (node (ref "P18") (pin "26") (pinfunction "26_26") (pintype "bidirectional"))
      (node (ref "P2") (pin "59") (pinfunction "59_59") (pintype "bidirectional"))
      (node (ref "P3") (pin "59") (pinfunction "59_59") (pintype "bidirectional"))
      (node (ref "P4") (pin "59") (pinfunction "59_59") (pintype "bidirectional"))
      (node (ref "P5") (pin "59") (pinfunction "59_59") (pintype "bidirectional"))
      (node (ref "P6") (pin "59") (pinfunction "59_59") (pintype "bidirectional"))
      (node (ref "P7") (pin "59") (pinfunction "59_59") (pintype "bidirectional"))
    )
    (net (code "194") (name "/PA7_B2") (class "Default")
      (node (ref "P10") (pin "59") (pinfunction "59_59") (pintype "bidirectional"))
      (node (ref "P11") (pin "59") (pinfunction "59_59") (pintype "bidirectional"))
      (node (ref "P12") (pin "59") (pinfunction "59_59") (pintype "bidirectional"))
      (node (ref "P13") (pin "59") (pinfunction "59_59") (pintype "bidirectional"))
      (node (ref "P14") (pin "59") (pinfunction "59_59") (pintype "bidirectional"))
      (node (ref "P15") (pin "59") (pinfunction "59_59") (pintype "bidirectional"))
      (node (ref "P16") (pin "61") (pinfunction "61_61") (pintype "bidirectional"))
      (node (ref "P8") (pin "59") (pinfunction "59_59") (pintype "bidirectional"))
      (node (ref "P9") (pin "59") (pinfunction "59_59") (pintype "bidirectional"))
    )
    (net (code "195") (name "/PA8_B1") (class "Default")
      (node (ref "P1") (pin "60") (pinfunction "60_60") (pintype "bidirectional"))
      (node (ref "P18") (pin "25") (pinfunction "25_25") (pintype "bidirectional"))
      (node (ref "P2") (pin "60") (pinfunction "60_60") (pintype "bidirectional"))
      (node (ref "P3") (pin "60") (pinfunction "60_60") (pintype "bidirectional"))
      (node (ref "P4") (pin "60") (pinfunction "60_60") (pintype "bidirectional"))
      (node (ref "P5") (pin "60") (pinfunction "60_60") (pintype "bidirectional"))
      (node (ref "P6") (pin "60") (pinfunction "60_60") (pintype "bidirectional"))
      (node (ref "P7") (pin "60") (pinfunction "60_60") (pintype "bidirectional"))
    )
    (net (code "196") (name "/PA8_B2") (class "Default")
      (node (ref "P10") (pin "60") (pinfunction "60_60") (pintype "bidirectional"))
      (node (ref "P11") (pin "60") (pinfunction "60_60") (pintype "bidirectional"))
      (node (ref "P12") (pin "60") (pinfunction "60_60") (pintype "bidirectional"))
      (node (ref "P13") (pin "60") (pinfunction "60_60") (pintype "bidirectional"))
      (node (ref "P14") (pin "60") (pinfunction "60_60") (pintype "bidirectional"))
      (node (ref "P15") (pin "60") (pinfunction "60_60") (pintype "bidirectional"))
      (node (ref "P16") (pin "60") (pinfunction "60_60") (pintype "bidirectional"))
      (node (ref "P8") (pin "60") (pinfunction "60_60") (pintype "bidirectional"))
      (node (ref "P9") (pin "60") (pinfunction "60_60") (pintype "bidirectional"))
    )
    (net (code "197") (name "/PA9_B1") (class "Default")
      (node (ref "P1") (pin "61") (pinfunction "61_61") (pintype "bidirectional"))
      (node (ref "P18") (pin "24") (pinfunction "24_24") (pintype "bidirectional"))
      (node (ref "P2") (pin "61") (pinfunction "61_61") (pintype "bidirectional"))
      (node (ref "P3") (pin "61") (pinfunction "61_61") (pintype "bidirectional"))
      (node (ref "P4") (pin "61") (pinfunction "61_61") (pintype "bidirectional"))
      (node (ref "P5") (pin "61") (pinfunction "61_61") (pintype "bidirectional"))
      (node (ref "P6") (pin "61") (pinfunction "61_61") (pintype "bidirectional"))
      (node (ref "P7") (pin "61") (pinfunction "61_61") (pintype "bidirectional"))
    )
    (net (code "198") (name "/PA9_B2") (class "Default")
      (node (ref "P10") (pin "61") (pinfunction "61_61") (pintype "bidirectional"))
      (node (ref "P11") (pin "61") (pinfunction "61_61") (pintype "bidirectional"))
      (node (ref "P12") (pin "61") (pinfunction "61_61") (pintype "bidirectional"))
      (node (ref "P13") (pin "61") (pinfunction "61_61") (pintype "bidirectional"))
      (node (ref "P14") (pin "61") (pinfunction "61_61") (pintype "bidirectional"))
      (node (ref "P15") (pin "61") (pinfunction "61_61") (pintype "bidirectional"))
      (node (ref "P16") (pin "59") (pinfunction "59_59") (pintype "bidirectional"))
      (node (ref "P8") (pin "61") (pinfunction "61_61") (pintype "bidirectional"))
      (node (ref "P9") (pin "61") (pinfunction "61_61") (pintype "bidirectional"))
    )
    (net (code "199") (name "/PA10_B1") (class "Default")
      (node (ref "P1") (pin "63") (pinfunction "63_63") (pintype "bidirectional"))
      (node (ref "P18") (pin "22") (pinfunction "22_22") (pintype "bidirectional"))
      (node (ref "P2") (pin "63") (pinfunction "63_63") (pintype "bidirectional"))
      (node (ref "P3") (pin "63") (pinfunction "63_63") (pintype "bidirectional"))
      (node (ref "P4") (pin "63") (pinfunction "63_63") (pintype "bidirectional"))
      (node (ref "P5") (pin "63") (pinfunction "63_63") (pintype "bidirectional"))
      (node (ref "P6") (pin "63") (pinfunction "63_63") (pintype "bidirectional"))
      (node (ref "P7") (pin "63") (pinfunction "63_63") (pintype "bidirectional"))
    )
    (net (code "200") (name "/PA10_B2") (class "Default")
      (node (ref "P10") (pin "63") (pinfunction "63_63") (pintype "bidirectional"))
      (node (ref "P11") (pin "63") (pinfunction "63_63") (pintype "bidirectional"))
      (node (ref "P12") (pin "63") (pinfunction "63_63") (pintype "bidirectional"))
      (node (ref "P13") (pin "63") (pinfunction "63_63") (pintype "bidirectional"))
      (node (ref "P14") (pin "63") (pinfunction "63_63") (pintype "bidirectional"))
      (node (ref "P15") (pin "63") (pinfunction "63_63") (pintype "bidirectional"))
      (node (ref "P16") (pin "58") (pinfunction "58_58") (pintype "bidirectional"))
      (node (ref "P8") (pin "63") (pinfunction "63_63") (pintype "bidirectional"))
      (node (ref "P9") (pin "63") (pinfunction "63_63") (pintype "bidirectional"))
    )
    (net (code "201") (name "/PA11_B1") (class "Default")
      (node (ref "P1") (pin "62") (pinfunction "62_62") (pintype "bidirectional"))
      (node (ref "P18") (pin "23") (pinfunction "23_23") (pintype "bidirectional"))
      (node (ref "P2") (pin "62") (pinfunction "62_62") (pintype "bidirectional"))
      (node (ref "P3") (pin "62") (pinfunction "62_62") (pintype "bidirectional"))
      (node (ref "P4") (pin "62") (pinfunction "62_62") (pintype "bidirectional"))
      (node (ref "P5") (pin "62") (pinfunction "62_62") (pintype "bidirectional"))
      (node (ref "P6") (pin "62") (pinfunction "62_62") (pintype "bidirectional"))
      (node (ref "P7") (pin "62") (pinfunction "62_62") (pintype "bidirectional"))
    )
    (net (code "202") (name "/PA11_B2") (class "Default")
      (node (ref "P10") (pin "62") (pinfunction "62_62") (pintype "bidirectional"))
      (node (ref "P11") (pin "62") (pinfunction "62_62") (pintype "bidirectional"))
      (node (ref "P12") (pin "62") (pinfunction "62_62") (pintype "bidirectional"))
      (node (ref "P13") (pin "62") (pinfunction "62_62") (pintype "bidirectional"))
      (node (ref "P14") (pin "62") (pinfunction "62_62") (pintype "bidirectional"))
      (node (ref "P15") (pin "62") (pinfunction "62_62") (pintype "bidirectional"))
      (node (ref "P16") (pin "57") (pinfunction "57_57") (pintype "bidirectional"))
      (node (ref "P8") (pin "62") (pinfunction "62_62") (pintype "bidirectional"))
      (node (ref "P9") (pin "62") (pinfunction "62_62") (pintype "bidirectional"))
    )
    (net (code "203") (name "/PA12_B1") (class "Default")
      (node (ref "P18") (pin "21") (pinfunction "21_21") (pintype "bidirectional"))
    )
    (net (code "204") (name "/PA12_B2") (class "Default")
      (node (ref "P16") (pin "56") (pinfunction "56_56") (pintype "bidirectional"))
    )
    (net (code "205") (name "/PPU_A12_1") (class "Default")
      (node (ref "J1") (pin "4") (pinfunction "4_4") (pintype "passive"))
      (node (ref "P1") (pin "64") (pinfunction "64_64") (pintype "bidirectional"))
    )
    (net (code "206") (name "/PPU_A12_2") (class "Default")
      (node (ref "J1") (pin "9") (pinfunction "9_9") (pintype "passive"))
      (node (ref "P2") (pin "64") (pinfunction "64_64") (pintype "bidirectional"))
    )
    (net (code "207") (name "/PPU_A12_3") (class "Default")
      (node (ref "J1") (pin "14") (pinfunction "14_14") (pintype "passive"))
      (node (ref "P3") (pin "64") (pinfunction "64_64") (pintype "bidirectional"))
    )
    (net (code "208") (name "/PPU_A12_4") (class "Default")
      (node (ref "J1") (pin "19") (pinfunction "19_19") (pintype "passive"))
      (node (ref "P4") (pin "64") (pinfunction "64_64") (pintype "bidirectional"))
    )
    (net (code "209") (name "/PPU_A12_5") (class "Default")
      (node (ref "J1") (pin "24") (pinfunction "24_24") (pintype "passive"))
      (node (ref "P5") (pin "64") (pinfunction "64_64") (pintype "bidirectional"))
    )
    (net (code "210") (name "/PPU_A12_6") (class "Default")
      (node (ref "J2") (pin "4") (pinfunction "4_4") (pintype "passive"))
      (node (ref "P6") (pin "64") (pinfunction "64_64") (pintype "bidirectional"))
    )
    (net (code "211") (name "/PPU_A12_7") (class "Default")
      (node (ref "J2") (pin "9") (pinfunction "9_9") (pintype "passive"))
      (node (ref "P7") (pin "64") (pinfunction "64_64") (pintype "bidirectional"))
    )
    (net (code "212") (name "/PPU_A12_8") (class "Default")
      (node (ref "J2") (pin "14") (pinfunction "14_14") (pintype "passive"))
      (node (ref "P8") (pin "64") (pinfunction "64_64") (pintype "bidirectional"))
    )
    (net (code "213") (name "/PPU_A12_9") (class "Default")
      (node (ref "J2") (pin "19") (pinfunction "19_19") (pintype "passive"))
      (node (ref "P9") (pin "64") (pinfunction "64_64") (pintype "bidirectional"))
    )
    (net (code "214") (name "/PPU_A12_10") (class "Default")
      (node (ref "J2") (pin "24") (pinfunction "24_24") (pintype "passive"))
      (node (ref "P10") (pin "64") (pinfunction "64_64") (pintype "bidirectional"))
    )
    (net (code "215") (name "/PPU_A12_11") (class "Default")
      (node (ref "J3") (pin "4") (pinfunction "4_4") (pintype "passive"))
      (node (ref "P11") (pin "64") (pinfunction "64_64") (pintype "bidirectional"))
    )
    (net (code "216") (name "/PPU_A12_12") (class "Default")
      (node (ref "J3") (pin "9") (pinfunction "9_9") (pintype "passive"))
      (node (ref "P12") (pin "64") (pinfunction "64_64") (pintype "bidirectional"))
    )
    (net (code "217") (name "/PPU_A12_13") (class "Default")
      (node (ref "J3") (pin "14") (pinfunction "14_14") (pintype "passive"))
      (node (ref "P13") (pin "64") (pinfunction "64_64") (pintype "bidirectional"))
    )
    (net (code "218") (name "/PPU_A12_14") (class "Default")
      (node (ref "J3") (pin "19") (pinfunction "19_19") (pintype "passive"))
      (node (ref "P14") (pin "64") (pinfunction "64_64") (pintype "bidirectional"))
    )
    (net (code "219") (name "/PPU_A12_15") (class "Default")
      (node (ref "J3") (pin "24") (pinfunction "24_24") (pintype "passive"))
      (node (ref "P15") (pin "64") (pinfunction "64_64") (pintype "bidirectional"))
    )
    (net (code "220") (name "/PPU_{slash}A13_IN") (class "Default")
      (node (ref "J1") (pin "26") (pinfunction "26_26") (pintype "passive"))
      (node (ref "P1") (pin "58") (pinfunction "58_58") (pintype "bidirectional"))
      (node (ref "P10") (pin "58") (pinfunction "58_58") (pintype "bidirectional"))
      (node (ref "P11") (pin "58") (pinfunction "58_58") (pintype "bidirectional"))
      (node (ref "P12") (pin "58") (pinfunction "58_58") (pintype "bidirectional"))
      (node (ref "P13") (pin "58") (pinfunction "58_58") (pintype "bidirectional"))
      (node (ref "P14") (pin "58") (pinfunction "58_58") (pintype "bidirectional"))
      (node (ref "P15") (pin "58") (pinfunction "58_58") (pintype "bidirectional"))
      (node (ref "P2") (pin "58") (pinfunction "58_58") (pintype "bidirectional"))
      (node (ref "P3") (pin "58") (pinfunction "58_58") (pintype "bidirectional"))
      (node (ref "P4") (pin "58") (pinfunction "58_58") (pintype "bidirectional"))
      (node (ref "P5") (pin "58") (pinfunction "58_58") (pintype "bidirectional"))
      (node (ref "P6") (pin "58") (pinfunction "58_58") (pintype "bidirectional"))
      (node (ref "P7") (pin "58") (pinfunction "58_58") (pintype "bidirectional"))
      (node (ref "P8") (pin "58") (pinfunction "58_58") (pintype "bidirectional"))
      (node (ref "P9") (pin "58") (pinfunction "58_58") (pintype "bidirectional"))
    )
    (net (code "221") (name "/PPU_{slash}RD_1") (class "Default")
      (node (ref "J1") (pin "5") (pinfunction "5_5") (pintype "passive"))
      (node (ref "P1") (pin "21") (pinfunction "21_21") (pintype "bidirectional"))
    )
    (net (code "222") (name "/PPU_{slash}RD_2") (class "Default")
      (node (ref "J1") (pin "10") (pinfunction "10_10") (pintype "passive"))
      (node (ref "P2") (pin "21") (pinfunction "21_21") (pintype "bidirectional"))
    )
    (net (code "223") (name "/PPU_{slash}RD_3") (class "Default")
      (node (ref "J1") (pin "15") (pinfunction "15_15") (pintype "passive"))
      (node (ref "P3") (pin "21") (pinfunction "21_21") (pintype "bidirectional"))
    )
    (net (code "224") (name "/PPU_{slash}RD_4") (class "Default")
      (node (ref "J1") (pin "20") (pinfunction "20_20") (pintype "passive"))
      (node (ref "P4") (pin "21") (pinfunction "21_21") (pintype "bidirectional"))
    )
    (net (code "225") (name "/PPU_{slash}RD_5") (class "Default")
      (node (ref "J1") (pin "25") (pinfunction "25_25") (pintype "passive"))
      (node (ref "P5") (pin "21") (pinfunction "21_21") (pintype "bidirectional"))
    )
    (net (code "226") (name "/PPU_{slash}RD_6") (class "Default")
      (node (ref "J2") (pin "5") (pinfunction "5_5") (pintype "passive"))
      (node (ref "P6") (pin "21") (pinfunction "21_21") (pintype "bidirectional"))
    )
    (net (code "227") (name "/PPU_{slash}RD_7") (class "Default")
      (node (ref "J2") (pin "10") (pinfunction "10_10") (pintype "passive"))
      (node (ref "P7") (pin "21") (pinfunction "21_21") (pintype "bidirectional"))
    )
    (net (code "228") (name "/PPU_{slash}RD_8") (class "Default")
      (node (ref "J2") (pin "15") (pinfunction "15_15") (pintype "passive"))
      (node (ref "P8") (pin "21") (pinfunction "21_21") (pintype "bidirectional"))
    )
    (net (code "229") (name "/PPU_{slash}RD_9") (class "Default")
      (node (ref "J2") (pin "20") (pinfunction "20_20") (pintype "passive"))
      (node (ref "P9") (pin "21") (pinfunction "21_21") (pintype "bidirectional"))
    )
    (net (code "230") (name "/PPU_{slash}RD_10") (class "Default")
      (node (ref "J2") (pin "25") (pinfunction "25_25") (pintype "passive"))
      (node (ref "P10") (pin "21") (pinfunction "21_21") (pintype "bidirectional"))
    )
    (net (code "231") (name "/PPU_{slash}RD_11") (class "Default")
      (node (ref "J3") (pin "5") (pinfunction "5_5") (pintype "passive"))
      (node (ref "P11") (pin "21") (pinfunction "21_21") (pintype "bidirectional"))
    )
    (net (code "232") (name "/PPU_{slash}RD_12") (class "Default")
      (node (ref "J3") (pin "10") (pinfunction "10_10") (pintype "passive"))
      (node (ref "P12") (pin "21") (pinfunction "21_21") (pintype "bidirectional"))
    )
    (net (code "233") (name "/PPU_{slash}RD_13") (class "Default")
      (node (ref "J3") (pin "15") (pinfunction "15_15") (pintype "passive"))
      (node (ref "P13") (pin "21") (pinfunction "21_21") (pintype "bidirectional"))
    )
    (net (code "234") (name "/PPU_{slash}RD_14") (class "Default")
      (node (ref "J3") (pin "20") (pinfunction "20_20") (pintype "passive"))
      (node (ref "P14") (pin "21") (pinfunction "21_21") (pintype "bidirectional"))
    )
    (net (code "235") (name "/PPU_{slash}RD_15") (class "Default")
      (node (ref "J3") (pin "25") (pinfunction "25_25") (pintype "passive"))
      (node (ref "P15") (pin "21") (pinfunction "21_21") (pintype "bidirectional"))
    )
    (net (code "236") (name "/RS_1") (class "Default")
      (node (ref "P1") (pin "50") (pinfunction "50_50") (pintype "bidirectional"))
      (node (ref "P18") (pin "17") (pinfunction "17_17") (pintype "bidirectional"))
    )
    (net (code "237") (name "/RS_2") (class "Default")
      (node (ref "P18") (pin "16") (pinfunction "16_16") (pintype "bidirectional"))
      (node (ref "P2") (pin "50") (pinfunction "50_50") (pintype "bidirectional"))
    )
    (net (code "238") (name "/RS_3") (class "Default")
      (node (ref "P18") (pin "15") (pinfunction "15_15") (pintype "bidirectional"))
      (node (ref "P3") (pin "50") (pinfunction "50_50") (pintype "bidirectional"))
    )
    (net (code "239") (name "/RS_4") (class "Default")
      (node (ref "P18") (pin "14") (pinfunction "14_14") (pintype "bidirectional"))
      (node (ref "P4") (pin "50") (pinfunction "50_50") (pintype "bidirectional"))
    )
    (net (code "240") (name "/RS_5") (class "Default")
      (node (ref "P18") (pin "13") (pinfunction "13_13") (pintype "bidirectional"))
      (node (ref "P5") (pin "50") (pinfunction "50_50") (pintype "bidirectional"))
    )
    (net (code "241") (name "/RS_6") (class "Default")
      (node (ref "P18") (pin "12") (pinfunction "12_12") (pintype "bidirectional"))
      (node (ref "P6") (pin "50") (pinfunction "50_50") (pintype "bidirectional"))
    )
    (net (code "242") (name "/RS_7") (class "Default")
      (node (ref "P18") (pin "11") (pinfunction "11_11") (pintype "bidirectional"))
      (node (ref "P7") (pin "50") (pinfunction "50_50") (pintype "bidirectional"))
    )
    (net (code "243") (name "/RS_8") (class "Default")
      (node (ref "P18") (pin "10") (pinfunction "10_10") (pintype "bidirectional"))
      (node (ref "P8") (pin "50") (pinfunction "50_50") (pintype "bidirectional"))
    )
    (net (code "244") (name "/RS_9") (class "Default")
      (node (ref "P18") (pin "9") (pinfunction "9_9") (pintype "bidirectional"))
      (node (ref "P9") (pin "50") (pinfunction "50_50") (pintype "bidirectional"))
    )
    (net (code "245") (name "/RS_10") (class "Default")
      (node (ref "P10") (pin "50") (pinfunction "50_50") (pintype "bidirectional"))
      (node (ref "P18") (pin "8") (pinfunction "8_8") (pintype "bidirectional"))
    )
    (net (code "246") (name "/RS_11") (class "Default")
      (node (ref "P11") (pin "50") (pinfunction "50_50") (pintype "bidirectional"))
      (node (ref "P18") (pin "7") (pinfunction "7_7") (pintype "bidirectional"))
    )
    (net (code "247") (name "/RS_12") (class "Default")
      (node (ref "P12") (pin "50") (pinfunction "50_50") (pintype "bidirectional"))
      (node (ref "P18") (pin "6") (pinfunction "6_6") (pintype "bidirectional"))
    )
    (net (code "248") (name "/RS_13") (class "Default")
      (node (ref "P13") (pin "50") (pinfunction "50_50") (pintype "bidirectional"))
      (node (ref "P18") (pin "5") (pinfunction "5_5") (pintype "bidirectional"))
    )
    (net (code "249") (name "/RS_14") (class "Default")
      (node (ref "P14") (pin "50") (pinfunction "50_50") (pintype "bidirectional"))
      (node (ref "P18") (pin "4") (pinfunction "4_4") (pintype "bidirectional"))
    )
    (net (code "250") (name "/RS_15") (class "Default")
      (node (ref "P15") (pin "50") (pinfunction "50_50") (pintype "bidirectional"))
      (node (ref "P18") (pin "3") (pinfunction "3_3") (pintype "bidirectional"))
    )
    (net (code "251") (name "/R{slash}W_B1") (class "Default")
      (node (ref "P1") (pin "14") (pinfunction "14_14") (pintype "bidirectional"))
      (node (ref "P18") (pin "54") (pinfunction "54_54") (pintype "bidirectional"))
      (node (ref "P2") (pin "14") (pinfunction "14_14") (pintype "bidirectional"))
      (node (ref "P3") (pin "14") (pinfunction "14_14") (pintype "bidirectional"))
      (node (ref "P4") (pin "14") (pinfunction "14_14") (pintype "bidirectional"))
      (node (ref "P5") (pin "14") (pinfunction "14_14") (pintype "bidirectional"))
      (node (ref "P6") (pin "14") (pinfunction "14_14") (pintype "bidirectional"))
      (node (ref "P7") (pin "14") (pinfunction "14_14") (pintype "bidirectional"))
    )
    (net (code "252") (name "/R{slash}W_B2") (class "Default")
      (node (ref "P10") (pin "14") (pinfunction "14_14") (pintype "bidirectional"))
      (node (ref "P11") (pin "14") (pinfunction "14_14") (pintype "bidirectional"))
      (node (ref "P12") (pin "14") (pinfunction "14_14") (pintype "bidirectional"))
      (node (ref "P13") (pin "14") (pinfunction "14_14") (pintype "bidirectional"))
      (node (ref "P14") (pin "14") (pinfunction "14_14") (pintype "bidirectional"))
      (node (ref "P15") (pin "14") (pinfunction "14_14") (pintype "bidirectional"))
      (node (ref "P16") (pin "55") (pinfunction "55_55") (pintype "bidirectional"))
      (node (ref "P8") (pin "14") (pinfunction "14_14") (pintype "bidirectional"))
      (node (ref "P9") (pin "14") (pinfunction "14_14") (pintype "bidirectional"))
    )
    (net (code "253") (name "/{slash}W_B1") (class "Default")
      (node (ref "P1") (pin "56") (pinfunction "56_56") (pintype "bidirectional"))
      (node (ref "P18") (pin "53") (pinfunction "53_53") (pintype "bidirectional"))
      (node (ref "P2") (pin "56") (pinfunction "56_56") (pintype "bidirectional"))
      (node (ref "P3") (pin "56") (pinfunction "56_56") (pintype "bidirectional"))
      (node (ref "P4") (pin "56") (pinfunction "56_56") (pintype "bidirectional"))
      (node (ref "P5") (pin "56") (pinfunction "56_56") (pintype "bidirectional"))
      (node (ref "P6") (pin "56") (pinfunction "56_56") (pintype "bidirectional"))
      (node (ref "P7") (pin "56") (pinfunction "56_56") (pintype "bidirectional"))
    )
    (net (code "254") (name "/{slash}W_B2") (class "Default")
      (node (ref "P10") (pin "56") (pinfunction "56_56") (pintype "bidirectional"))
      (node (ref "P11") (pin "56") (pinfunction "56_56") (pintype "bidirectional"))
      (node (ref "P12") (pin "56") (pinfunction "56_56") (pintype "bidirectional"))
      (node (ref "P13") (pin "56") (pinfunction "56_56") (pintype "bidirectional"))
      (node (ref "P14") (pin "56") (pinfunction "56_56") (pintype "bidirectional"))
      (node (ref "P15") (pin "56") (pinfunction "56_56") (pintype "bidirectional"))
      (node (ref "P16") (pin "54") (pinfunction "54_54") (pintype "bidirectional"))
      (node (ref "P8") (pin "56") (pinfunction "56_56") (pintype "bidirectional"))
      (node (ref "P9") (pin "56") (pinfunction "56_56") (pintype "bidirectional"))
    )
    (net (code "255") (name "GND") (class "Default")
      (node (ref "C1") (pin "1") (pinfunction "1_1") (pintype "passive"))
      (node (ref "C10") (pin "-") (pinfunction "-_-") (pintype "passive"))
      (node (ref "C2") (pin "1") (pinfunction "1_1") (pintype "passive"))
      (node (ref "C3") (pin "1") (pinfunction "1_1") (pintype "passive"))
      (node (ref "C4") (pin "1") (pinfunction "1_1") (pintype "passive"))
      (node (ref "C5") (pin "1") (pinfunction "1_1") (pintype "passive"))
      (node (ref "C6") (pin "1") (pinfunction "1_1") (pintype "passive"))
      (node (ref "C7") (pin "1") (pinfunction "1_1") (pintype "passive"))
      (node (ref "C8") (pin "1") (pinfunction "1_1") (pintype "passive"))
      (node (ref "C9") (pin "-") (pinfunction "-_-") (pintype "passive"))
      (node (ref "P1") (pin "1") (pinfunction "1_1") (pintype "bidirectional"))
      (node (ref "P1") (pin "72") (pinfunction "72_72") (pintype "bidirectional"))
      (node (ref "P10") (pin "1") (pinfunction "1_1") (pintype "bidirectional"))
      (node (ref "P10") (pin "72") (pinfunction "72_72") (pintype "bidirectional"))
      (node (ref "P11") (pin "1") (pinfunction "1_1") (pintype "bidirectional"))
      (node (ref "P11") (pin "72") (pinfunction "72_72") (pintype "bidirectional"))
      (node (ref "P12") (pin "1") (pinfunction "1_1") (pintype "bidirectional"))
      (node (ref "P12") (pin "72") (pinfunction "72_72") (pintype "bidirectional"))
      (node (ref "P13") (pin "1") (pinfunction "1_1") (pintype "bidirectional"))
      (node (ref "P13") (pin "72") (pinfunction "72_72") (pintype "bidirectional"))
      (node (ref "P14") (pin "1") (pinfunction "1_1") (pintype "bidirectional"))
      (node (ref "P14") (pin "72") (pinfunction "72_72") (pintype "bidirectional"))
      (node (ref "P15") (pin "1") (pinfunction "1_1") (pintype "bidirectional"))
      (node (ref "P15") (pin "72") (pinfunction "72_72") (pintype "bidirectional"))
      (node (ref "P16") (pin "15") (pinfunction "15_15") (pintype "bidirectional"))
      (node (ref "P16") (pin "16") (pinfunction "16_16") (pintype "bidirectional"))
      (node (ref "P16") (pin "17") (pinfunction "17_17") (pintype "bidirectional"))
      (node (ref "P16") (pin "36") (pinfunction "36_36") (pintype "bidirectional"))
      (node (ref "P16") (pin "44") (pinfunction "44_44") (pintype "bidirectional"))
      (node (ref "P16") (pin "45") (pinfunction "45_45") (pintype "bidirectional"))
      (node (ref "P16") (pin "46") (pinfunction "46_46") (pintype "bidirectional"))
      (node (ref "P16") (pin "47") (pinfunction "47_47") (pintype "bidirectional"))
      (node (ref "P16") (pin "48") (pinfunction "48_48") (pintype "bidirectional"))
      (node (ref "P16") (pin "49") (pinfunction "49_49") (pintype "bidirectional"))
      (node (ref "P16") (pin "50") (pinfunction "50_50") (pintype "bidirectional"))
      (node (ref "P16") (pin "51") (pinfunction "51_51") (pintype "bidirectional"))
      (node (ref "P16") (pin "52") (pinfunction "52_52") (pintype "bidirectional"))
      (node (ref "P16") (pin "53") (pinfunction "53_53") (pintype "bidirectional"))
      (node (ref "P16") (pin "70") (pinfunction "70_70") (pintype "bidirectional"))
      (node (ref "P16") (pin "71") (pinfunction "71_71") (pintype "bidirectional"))
      (node (ref "P16") (pin "72") (pinfunction "72_72") (pintype "bidirectional"))
      (node (ref "P16") (pin "8") (pinfunction "8_8") (pintype "bidirectional"))
      (node (ref "P16") (pin "9") (pinfunction "9_9") (pintype "bidirectional"))
      (node (ref "P17") (pin "35") (pinfunction "35_35") (pintype "bidirectional"))
      (node (ref "P17") (pin "36") (pinfunction "36_36") (pintype "bidirectional"))
      (node (ref "P17") (pin "70") (pinfunction "70_70") (pintype "bidirectional"))
      (node (ref "P17") (pin "71") (pinfunction "71_71") (pintype "bidirectional"))
      (node (ref "P17") (pin "72") (pinfunction "72_72") (pintype "bidirectional"))
      (node (ref "P18") (pin "36") (pinfunction "36_36") (pintype "bidirectional"))
      (node (ref "P18") (pin "71") (pinfunction "71_71") (pintype "bidirectional"))
      (node (ref "P18") (pin "72") (pinfunction "72_72") (pintype "bidirectional"))
      (node (ref "P2") (pin "1") (pinfunction "1_1") (pintype "bidirectional"))
      (node (ref "P2") (pin "72") (pinfunction "72_72") (pintype "bidirectional"))
      (node (ref "P3") (pin "1") (pinfunction "1_1") (pintype "bidirectional"))
      (node (ref "P3") (pin "72") (pinfunction "72_72") (pintype "bidirectional"))
      (node (ref "P4") (pin "1") (pinfunction "1_1") (pintype "bidirectional"))
      (node (ref "P4") (pin "72") (pinfunction "72_72") (pintype "bidirectional"))
      (node (ref "P5") (pin "1") (pinfunction "1_1") (pintype "bidirectional"))
      (node (ref "P5") (pin "72") (pinfunction "72_72") (pintype "bidirectional"))
      (node (ref "P6") (pin "1") (pinfunction "1_1") (pintype "bidirectional"))
      (node (ref "P6") (pin "72") (pinfunction "72_72") (pintype "bidirectional"))
      (node (ref "P7") (pin "1") (pinfunction "1_1") (pintype "bidirectional"))
      (node (ref "P7") (pin "72") (pinfunction "72_72") (pintype "bidirectional"))
      (node (ref "P8") (pin "1") (pinfunction "1_1") (pintype "bidirectional"))
      (node (ref "P8") (pin "72") (pinfunction "72_72") (pintype "bidirectional"))
      (node (ref "P9") (pin "1") (pinfunction "1_1") (pintype "bidirectional"))
      (node (ref "P9") (pin "72") (pinfunction "72_72") (pintype "bidirectional"))
    )
    (net (code "256") (name "VCC") (class "Default")
      (node (ref "C1") (pin "2") (pinfunction "2_2") (pintype "passive"))
      (node (ref "C10") (pin "+") (pinfunction "+_+") (pintype "passive"))
      (node (ref "C2") (pin "2") (pinfunction "2_2") (pintype "passive"))
      (node (ref "C3") (pin "2") (pinfunction "2_2") (pintype "passive"))
      (node (ref "C4") (pin "2") (pinfunction "2_2") (pintype "passive"))
      (node (ref "C5") (pin "2") (pinfunction "2_2") (pintype "passive"))
      (node (ref "C6") (pin "2") (pinfunction "2_2") (pintype "passive"))
      (node (ref "C7") (pin "2") (pinfunction "2_2") (pintype "passive"))
      (node (ref "C8") (pin "2") (pinfunction "2_2") (pintype "passive"))
      (node (ref "C9") (pin "+") (pinfunction "+_+") (pintype "passive"))
      (node (ref "P1") (pin "36") (pinfunction "36_36") (pintype "bidirectional"))
      (node (ref "P10") (pin "36") (pinfunction "36_36") (pintype "bidirectional"))
      (node (ref "P11") (pin "36") (pinfunction "36_36") (pintype "bidirectional"))
      (node (ref "P12") (pin "36") (pinfunction "36_36") (pintype "bidirectional"))
      (node (ref "P13") (pin "36") (pinfunction "36_36") (pintype "bidirectional"))
      (node (ref "P14") (pin "36") (pinfunction "36_36") (pintype "bidirectional"))
      (node (ref "P15") (pin "36") (pinfunction "36_36") (pintype "bidirectional"))
      (node (ref "P16") (pin "1") (pinfunction "1_1") (pintype "bidirectional"))
      (node (ref "P16") (pin "2") (pinfunction "2_2") (pintype "bidirectional"))
      (node (ref "P16") (pin "37") (pinfunction "37_37") (pintype "bidirectional"))
      (node (ref "P16") (pin "38") (pinfunction "38_38") (pintype "bidirectional"))
      (node (ref "P16") (pin "39") (pinfunction "39_39") (pintype "bidirectional"))
      (node (ref "P16") (pin "40") (pinfunction "40_40") (pintype "bidirectional"))
      (node (ref "P16") (pin "41") (pinfunction "41_41") (pintype "bidirectional"))
      (node (ref "P16") (pin "42") (pinfunction "42_42") (pintype "bidirectional"))
      (node (ref "P16") (pin "43") (pinfunction "43_43") (pintype "bidirectional"))
      (node (ref "P17") (pin "1") (pinfunction "1_1") (pintype "bidirectional"))
      (node (ref "P17") (pin "2") (pinfunction "2_2") (pintype "bidirectional"))
      (node (ref "P17") (pin "37") (pinfunction "37_37") (pintype "bidirectional"))
      (node (ref "P17") (pin "38") (pinfunction "38_38") (pintype "bidirectional"))
      (node (ref "P18") (pin "1") (pinfunction "1_1") (pintype "bidirectional"))
      (node (ref "P18") (pin "2") (pinfunction "2_2") (pintype "bidirectional"))
      (node (ref "P18") (pin "37") (pinfunction "37_37") (pintype "bidirectional"))
      (node (ref "P2") (pin "36") (pinfunction "36_36") (pintype "bidirectional"))
      (node (ref "P3") (pin "36") (pinfunction "36_36") (pintype "bidirectional"))
      (node (ref "P4") (pin "36") (pinfunction "36_36") (pintype "bidirectional"))
      (node (ref "P5") (pin "36") (pinfunction "36_36") (pintype "bidirectional"))
      (node (ref "P6") (pin "36") (pinfunction "36_36") (pintype "bidirectional"))
      (node (ref "P7") (pin "36") (pinfunction "36_36") (pintype "bidirectional"))
      (node (ref "P8") (pin "36") (pinfunction "36_36") (pintype "bidirectional"))
      (node (ref "P9") (pin "36") (pinfunction "36_36") (pintype "bidirectional"))
    )
    (net (code "257") (name "unconnected-(J2-Pad26)") (class "Default")
      (node (ref "J2") (pin "26") (pinfunction "26_26") (pintype "passive"))
    )
    (net (code "258") (name "unconnected-(J3-Pad26)") (class "Default")
      (node (ref "J3") (pin "26") (pinfunction "26_26") (pintype "passive"))
    )
    (net (code "259") (name "unconnected-(P1-Pad16)") (class "Default")
      (node (ref "P1") (pin "16") (pinfunction "16_16") (pintype "bidirectional"))
    )
    (net (code "260") (name "unconnected-(P1-Pad17)") (class "Default")
      (node (ref "P1") (pin "17") (pinfunction "17_17") (pintype "bidirectional"))
    )
    (net (code "261") (name "unconnected-(P1-Pad18)") (class "Default")
      (node (ref "P1") (pin "18") (pinfunction "18_18") (pintype "bidirectional"))
    )
    (net (code "262") (name "unconnected-(P1-Pad19)") (class "Default")
      (node (ref "P1") (pin "19") (pinfunction "19_19") (pintype "bidirectional"))
    )
    (net (code "263") (name "unconnected-(P1-Pad20)") (class "Default")
      (node (ref "P1") (pin "20") (pinfunction "20_20") (pintype "bidirectional"))
    )
    (net (code "264") (name "unconnected-(P1-Pad34)") (class "Default")
      (node (ref "P1") (pin "34") (pinfunction "34_34") (pintype "bidirectional"))
    )
    (net (code "265") (name "unconnected-(P1-Pad35)") (class "Default")
      (node (ref "P1") (pin "35") (pinfunction "35_35") (pintype "bidirectional"))
    )
    (net (code "266") (name "unconnected-(P1-Pad37)") (class "Default")
      (node (ref "P1") (pin "37") (pinfunction "37_37") (pintype "bidirectional"))
    )
    (net (code "267") (name "unconnected-(P1-Pad51)") (class "Default")
      (node (ref "P1") (pin "51") (pinfunction "51_51") (pintype "bidirectional"))
    )
    (net (code "268") (name "unconnected-(P1-Pad52)") (class "Default")
      (node (ref "P1") (pin "52") (pinfunction "52_52") (pintype "bidirectional"))
    )
    (net (code "269") (name "unconnected-(P1-Pad53)") (class "Default")
      (node (ref "P1") (pin "53") (pinfunction "53_53") (pintype "bidirectional"))
    )
    (net (code "270") (name "unconnected-(P1-Pad55)") (class "Default")
      (node (ref "P1") (pin "55") (pinfunction "55_55") (pintype "bidirectional"))
    )
    (net (code "271") (name "unconnected-(P1-Pad70)") (class "Default")
      (node (ref "P1") (pin "70") (pinfunction "70_70") (pintype "bidirectional"))
    )
    (net (code "272") (name "unconnected-(P1-Pad71)") (class "Default")
      (node (ref "P1") (pin "71") (pinfunction "71_71") (pintype "bidirectional"))
    )
    (net (code "273") (name "unconnected-(P2-Pad16)") (class "Default")
      (node (ref "P2") (pin "16") (pinfunction "16_16") (pintype "bidirectional"))
    )
    (net (code "274") (name "unconnected-(P2-Pad17)") (class "Default")
      (node (ref "P2") (pin "17") (pinfunction "17_17") (pintype "bidirectional"))
    )
    (net (code "275") (name "unconnected-(P2-Pad18)") (class "Default")
      (node (ref "P2") (pin "18") (pinfunction "18_18") (pintype "bidirectional"))
    )
    (net (code "276") (name "unconnected-(P2-Pad19)") (class "Default")
      (node (ref "P2") (pin "19") (pinfunction "19_19") (pintype "bidirectional"))
    )
    (net (code "277") (name "unconnected-(P2-Pad20)") (class "Default")
      (node (ref "P2") (pin "20") (pinfunction "20_20") (pintype "bidirectional"))
    )
    (net (code "278") (name "unconnected-(P2-Pad34)") (class "Default")
      (node (ref "P2") (pin "34") (pinfunction "34_34") (pintype "bidirectional"))
    )
    (net (code "279") (name "unconnected-(P2-Pad35)") (class "Default")
      (node (ref "P2") (pin "35") (pinfunction "35_35") (pintype "bidirectional"))
    )
    (net (code "280") (name "unconnected-(P2-Pad37)") (class "Default")
      (node (ref "P2") (pin "37") (pinfunction "37_37") (pintype "bidirectional"))
    )
    (net (code "281") (name "unconnected-(P2-Pad51)") (class "Default")
      (node (ref "P2") (pin "51") (pinfunction "51_51") (pintype "bidirectional"))
    )
    (net (code "282") (name "unconnected-(P2-Pad52)") (class "Default")
      (node (ref "P2") (pin "52") (pinfunction "52_52") (pintype "bidirectional"))
    )
    (net (code "283") (name "unconnected-(P2-Pad53)") (class "Default")
      (node (ref "P2") (pin "53") (pinfunction "53_53") (pintype "bidirectional"))
    )
    (net (code "284") (name "unconnected-(P2-Pad55)") (class "Default")
      (node (ref "P2") (pin "55") (pinfunction "55_55") (pintype "bidirectional"))
    )
    (net (code "285") (name "unconnected-(P2-Pad70)") (class "Default")
      (node (ref "P2") (pin "70") (pinfunction "70_70") (pintype "bidirectional"))
    )
    (net (code "286") (name "unconnected-(P2-Pad71)") (class "Default")
      (node (ref "P2") (pin "71") (pinfunction "71_71") (pintype "bidirectional"))
    )
    (net (code "287") (name "unconnected-(P3-Pad16)") (class "Default")
      (node (ref "P3") (pin "16") (pinfunction "16_16") (pintype "bidirectional"))
    )
    (net (code "288") (name "unconnected-(P3-Pad17)") (class "Default")
      (node (ref "P3") (pin "17") (pinfunction "17_17") (pintype "bidirectional"))
    )
    (net (code "289") (name "unconnected-(P3-Pad18)") (class "Default")
      (node (ref "P3") (pin "18") (pinfunction "18_18") (pintype "bidirectional"))
    )
    (net (code "290") (name "unconnected-(P3-Pad19)") (class "Default")
      (node (ref "P3") (pin "19") (pinfunction "19_19") (pintype "bidirectional"))
    )
    (net (code "291") (name "unconnected-(P3-Pad20)") (class "Default")
      (node (ref "P3") (pin "20") (pinfunction "20_20") (pintype "bidirectional"))
    )
    (net (code "292") (name "unconnected-(P3-Pad34)") (class "Default")
      (node (ref "P3") (pin "34") (pinfunction "34_34") (pintype "bidirectional"))
    )
    (net (code "293") (name "unconnected-(P3-Pad35)") (class "Default")
      (node (ref "P3") (pin "35") (pinfunction "35_35") (pintype "bidirectional"))
    )
    (net (code "294") (name "unconnected-(P3-Pad37)") (class "Default")
      (node (ref "P3") (pin "37") (pinfunction "37_37") (pintype "bidirectional"))
    )
    (net (code "295") (name "unconnected-(P3-Pad51)") (class "Default")
      (node (ref "P3") (pin "51") (pinfunction "51_51") (pintype "bidirectional"))
    )
    (net (code "296") (name "unconnected-(P3-Pad52)") (class "Default")
      (node (ref "P3") (pin "52") (pinfunction "52_52") (pintype "bidirectional"))
    )
    (net (code "297") (name "unconnected-(P3-Pad53)") (class "Default")
      (node (ref "P3") (pin "53") (pinfunction "53_53") (pintype "bidirectional"))
    )
    (net (code "298") (name "unconnected-(P3-Pad55)") (class "Default")
      (node (ref "P3") (pin "55") (pinfunction "55_55") (pintype "bidirectional"))
    )
    (net (code "299") (name "unconnected-(P3-Pad70)") (class "Default")
      (node (ref "P3") (pin "70") (pinfunction "70_70") (pintype "bidirectional"))
    )
    (net (code "300") (name "unconnected-(P3-Pad71)") (class "Default")
      (node (ref "P3") (pin "71") (pinfunction "71_71") (pintype "bidirectional"))
    )
    (net (code "301") (name "unconnected-(P4-Pad16)") (class "Default")
      (node (ref "P4") (pin "16") (pinfunction "16_16") (pintype "bidirectional"))
    )
    (net (code "302") (name "unconnected-(P4-Pad17)") (class "Default")
      (node (ref "P4") (pin "17") (pinfunction "17_17") (pintype "bidirectional"))
    )
    (net (code "303") (name "unconnected-(P4-Pad18)") (class "Default")
      (node (ref "P4") (pin "18") (pinfunction "18_18") (pintype "bidirectional"))
    )
    (net (code "304") (name "unconnected-(P4-Pad19)") (class "Default")
      (node (ref "P4") (pin "19") (pinfunction "19_19") (pintype "bidirectional"))
    )
    (net (code "305") (name "unconnected-(P4-Pad20)") (class "Default")
      (node (ref "P4") (pin "20") (pinfunction "20_20") (pintype "bidirectional"))
    )
    (net (code "306") (name "unconnected-(P4-Pad34)") (class "Default")
      (node (ref "P4") (pin "34") (pinfunction "34_34") (pintype "bidirectional"))
    )
    (net (code "307") (name "unconnected-(P4-Pad35)") (class "Default")
      (node (ref "P4") (pin "35") (pinfunction "35_35") (pintype "bidirectional"))
    )
    (net (code "308") (name "unconnected-(P4-Pad37)") (class "Default")
      (node (ref "P4") (pin "37") (pinfunction "37_37") (pintype "bidirectional"))
    )
    (net (code "309") (name "unconnected-(P4-Pad51)") (class "Default")
      (node (ref "P4") (pin "51") (pinfunction "51_51") (pintype "bidirectional"))
    )
    (net (code "310") (name "unconnected-(P4-Pad52)") (class "Default")
      (node (ref "P4") (pin "52") (pinfunction "52_52") (pintype "bidirectional"))
    )
    (net (code "311") (name "unconnected-(P4-Pad53)") (class "Default")
      (node (ref "P4") (pin "53") (pinfunction "53_53") (pintype "bidirectional"))
    )
    (net (code "312") (name "unconnected-(P4-Pad55)") (class "Default")
      (node (ref "P4") (pin "55") (pinfunction "55_55") (pintype "bidirectional"))
    )
    (net (code "313") (name "unconnected-(P4-Pad70)") (class "Default")
      (node (ref "P4") (pin "70") (pinfunction "70_70") (pintype "bidirectional"))
    )
    (net (code "314") (name "unconnected-(P4-Pad71)") (class "Default")
      (node (ref "P4") (pin "71") (pinfunction "71_71") (pintype "bidirectional"))
    )
    (net (code "315") (name "unconnected-(P5-Pad16)") (class "Default")
      (node (ref "P5") (pin "16") (pinfunction "16_16") (pintype "bidirectional"))
    )
    (net (code "316") (name "unconnected-(P5-Pad17)") (class "Default")
      (node (ref "P5") (pin "17") (pinfunction "17_17") (pintype "bidirectional"))
    )
    (net (code "317") (name "unconnected-(P5-Pad18)") (class "Default")
      (node (ref "P5") (pin "18") (pinfunction "18_18") (pintype "bidirectional"))
    )
    (net (code "318") (name "unconnected-(P5-Pad19)") (class "Default")
      (node (ref "P5") (pin "19") (pinfunction "19_19") (pintype "bidirectional"))
    )
    (net (code "319") (name "unconnected-(P5-Pad20)") (class "Default")
      (node (ref "P5") (pin "20") (pinfunction "20_20") (pintype "bidirectional"))
    )
    (net (code "320") (name "unconnected-(P5-Pad34)") (class "Default")
      (node (ref "P5") (pin "34") (pinfunction "34_34") (pintype "bidirectional"))
    )
    (net (code "321") (name "unconnected-(P5-Pad35)") (class "Default")
      (node (ref "P5") (pin "35") (pinfunction "35_35") (pintype "bidirectional"))
    )
    (net (code "322") (name "unconnected-(P5-Pad37)") (class "Default")
      (node (ref "P5") (pin "37") (pinfunction "37_37") (pintype "bidirectional"))
    )
    (net (code "323") (name "unconnected-(P5-Pad51)") (class "Default")
      (node (ref "P5") (pin "51") (pinfunction "51_51") (pintype "bidirectional"))
    )
    (net (code "324") (name "unconnected-(P5-Pad52)") (class "Default")
      (node (ref "P5") (pin "52") (pinfunction "52_52") (pintype "bidirectional"))
    )
    (net (code "325") (name "unconnected-(P5-Pad53)") (class "Default")
      (node (ref "P5") (pin "53") (pinfunction "53_53") (pintype "bidirectional"))
    )
    (net (code "326") (name "unconnected-(P5-Pad55)") (class "Default")
      (node (ref "P5") (pin "55") (pinfunction "55_55") (pintype "bidirectional"))
    )
    (net (code "327") (name "unconnected-(P5-Pad70)") (class "Default")
      (node (ref "P5") (pin "70") (pinfunction "70_70") (pintype "bidirectional"))
    )
    (net (code "328") (name "unconnected-(P5-Pad71)") (class "Default")
      (node (ref "P5") (pin "71") (pinfunction "71_71") (pintype "bidirectional"))
    )
    (net (code "329") (name "unconnected-(P6-Pad16)") (class "Default")
      (node (ref "P6") (pin "16") (pinfunction "16_16") (pintype "bidirectional"))
    )
    (net (code "330") (name "unconnected-(P6-Pad17)") (class "Default")
      (node (ref "P6") (pin "17") (pinfunction "17_17") (pintype "bidirectional"))
    )
    (net (code "331") (name "unconnected-(P6-Pad18)") (class "Default")
      (node (ref "P6") (pin "18") (pinfunction "18_18") (pintype "bidirectional"))
    )
    (net (code "332") (name "unconnected-(P6-Pad19)") (class "Default")
      (node (ref "P6") (pin "19") (pinfunction "19_19") (pintype "bidirectional"))
    )
    (net (code "333") (name "unconnected-(P6-Pad20)") (class "Default")
      (node (ref "P6") (pin "20") (pinfunction "20_20") (pintype "bidirectional"))
    )
    (net (code "334") (name "unconnected-(P6-Pad34)") (class "Default")
      (node (ref "P6") (pin "34") (pinfunction "34_34") (pintype "bidirectional"))
    )
    (net (code "335") (name "unconnected-(P6-Pad35)") (class "Default")
      (node (ref "P6") (pin "35") (pinfunction "35_35") (pintype "bidirectional"))
    )
    (net (code "336") (name "unconnected-(P6-Pad37)") (class "Default")
      (node (ref "P6") (pin "37") (pinfunction "37_37") (pintype "bidirectional"))
    )
    (net (code "337") (name "unconnected-(P6-Pad51)") (class "Default")
      (node (ref "P6") (pin "51") (pinfunction "51_51") (pintype "bidirectional"))
    )
    (net (code "338") (name "unconnected-(P6-Pad52)") (class "Default")
      (node (ref "P6") (pin "52") (pinfunction "52_52") (pintype "bidirectional"))
    )
    (net (code "339") (name "unconnected-(P6-Pad53)") (class "Default")
      (node (ref "P6") (pin "53") (pinfunction "53_53") (pintype "bidirectional"))
    )
    (net (code "340") (name "unconnected-(P6-Pad55)") (class "Default")
      (node (ref "P6") (pin "55") (pinfunction "55_55") (pintype "bidirectional"))
    )
    (net (code "341") (name "unconnected-(P6-Pad70)") (class "Default")
      (node (ref "P6") (pin "70") (pinfunction "70_70") (pintype "bidirectional"))
    )
    (net (code "342") (name "unconnected-(P6-Pad71)") (class "Default")
      (node (ref "P6") (pin "71") (pinfunction "71_71") (pintype "bidirectional"))
    )
    (net (code "343") (name "unconnected-(P7-Pad16)") (class "Default")
      (node (ref "P7") (pin "16") (pinfunction "16_16") (pintype "bidirectional"))
    )
    (net (code "344") (name "unconnected-(P7-Pad17)") (class "Default")
      (node (ref "P7") (pin "17") (pinfunction "17_17") (pintype "bidirectional"))
    )
    (net (code "345") (name "unconnected-(P7-Pad18)") (class "Default")
      (node (ref "P7") (pin "18") (pinfunction "18_18") (pintype "bidirectional"))
    )
    (net (code "346") (name "unconnected-(P7-Pad19)") (class "Default")
      (node (ref "P7") (pin "19") (pinfunction "19_19") (pintype "bidirectional"))
    )
    (net (code "347") (name "unconnected-(P7-Pad20)") (class "Default")
      (node (ref "P7") (pin "20") (pinfunction "20_20") (pintype "bidirectional"))
    )
    (net (code "348") (name "unconnected-(P7-Pad34)") (class "Default")
      (node (ref "P7") (pin "34") (pinfunction "34_34") (pintype "bidirectional"))
    )
    (net (code "349") (name "unconnected-(P7-Pad35)") (class "Default")
      (node (ref "P7") (pin "35") (pinfunction "35_35") (pintype "bidirectional"))
    )
    (net (code "350") (name "unconnected-(P7-Pad37)") (class "Default")
      (node (ref "P7") (pin "37") (pinfunction "37_37") (pintype "bidirectional"))
    )
    (net (code "351") (name "unconnected-(P7-Pad51)") (class "Default")
      (node (ref "P7") (pin "51") (pinfunction "51_51") (pintype "bidirectional"))
    )
    (net (code "352") (name "unconnected-(P7-Pad52)") (class "Default")
      (node (ref "P7") (pin "52") (pinfunction "52_52") (pintype "bidirectional"))
    )
    (net (code "353") (name "unconnected-(P7-Pad53)") (class "Default")
      (node (ref "P7") (pin "53") (pinfunction "53_53") (pintype "bidirectional"))
    )
    (net (code "354") (name "unconnected-(P7-Pad55)") (class "Default")
      (node (ref "P7") (pin "55") (pinfunction "55_55") (pintype "bidirectional"))
    )
    (net (code "355") (name "unconnected-(P7-Pad70)") (class "Default")
      (node (ref "P7") (pin "70") (pinfunction "70_70") (pintype "bidirectional"))
    )
    (net (code "356") (name "unconnected-(P7-Pad71)") (class "Default")
      (node (ref "P7") (pin "71") (pinfunction "71_71") (pintype "bidirectional"))
    )
    (net (code "357") (name "unconnected-(P8-Pad16)") (class "Default")
      (node (ref "P8") (pin "16") (pinfunction "16_16") (pintype "bidirectional"))
    )
    (net (code "358") (name "unconnected-(P8-Pad17)") (class "Default")
      (node (ref "P8") (pin "17") (pinfunction "17_17") (pintype "bidirectional"))
    )
    (net (code "359") (name "unconnected-(P8-Pad18)") (class "Default")
      (node (ref "P8") (pin "18") (pinfunction "18_18") (pintype "bidirectional"))
    )
    (net (code "360") (name "unconnected-(P8-Pad19)") (class "Default")
      (node (ref "P8") (pin "19") (pinfunction "19_19") (pintype "bidirectional"))
    )
    (net (code "361") (name "unconnected-(P8-Pad20)") (class "Default")
      (node (ref "P8") (pin "20") (pinfunction "20_20") (pintype "bidirectional"))
    )
    (net (code "362") (name "unconnected-(P8-Pad34)") (class "Default")
      (node (ref "P8") (pin "34") (pinfunction "34_34") (pintype "bidirectional"))
    )
    (net (code "363") (name "unconnected-(P8-Pad35)") (class "Default")
      (node (ref "P8") (pin "35") (pinfunction "35_35") (pintype "bidirectional"))
    )
    (net (code "364") (name "unconnected-(P8-Pad37)") (class "Default")
      (node (ref "P8") (pin "37") (pinfunction "37_37") (pintype "bidirectional"))
    )
    (net (code "365") (name "unconnected-(P8-Pad51)") (class "Default")
      (node (ref "P8") (pin "51") (pinfunction "51_51") (pintype "bidirectional"))
    )
    (net (code "366") (name "unconnected-(P8-Pad52)") (class "Default")
      (node (ref "P8") (pin "52") (pinfunction "52_52") (pintype "bidirectional"))
    )
    (net (code "367") (name "unconnected-(P8-Pad53)") (class "Default")
      (node (ref "P8") (pin "53") (pinfunction "53_53") (pintype "bidirectional"))
    )
    (net (code "368") (name "unconnected-(P8-Pad55)") (class "Default")
      (node (ref "P8") (pin "55") (pinfunction "55_55") (pintype "bidirectional"))
    )
    (net (code "369") (name "unconnected-(P8-Pad70)") (class "Default")
      (node (ref "P8") (pin "70") (pinfunction "70_70") (pintype "bidirectional"))
    )
    (net (code "370") (name "unconnected-(P8-Pad71)") (class "Default")
      (node (ref "P8") (pin "71") (pinfunction "71_71") (pintype "bidirectional"))
    )
    (net (code "371") (name "unconnected-(P9-Pad16)") (class "Default")
      (node (ref "P9") (pin "16") (pinfunction "16_16") (pintype "bidirectional"))
    )
    (net (code "372") (name "unconnected-(P9-Pad17)") (class "Default")
      (node (ref "P9") (pin "17") (pinfunction "17_17") (pintype "bidirectional"))
    )
    (net (code "373") (name "unconnected-(P9-Pad18)") (class "Default")
      (node (ref "P9") (pin "18") (pinfunction "18_18") (pintype "bidirectional"))
    )
    (net (code "374") (name "unconnected-(P9-Pad19)") (class "Default")
      (node (ref "P9") (pin "19") (pinfunction "19_19") (pintype "bidirectional"))
    )
    (net (code "375") (name "unconnected-(P9-Pad20)") (class "Default")
      (node (ref "P9") (pin "20") (pinfunction "20_20") (pintype "bidirectional"))
    )
    (net (code "376") (name "unconnected-(P9-Pad34)") (class "Default")
      (node (ref "P9") (pin "34") (pinfunction "34_34") (pintype "bidirectional"))
    )
    (net (code "377") (name "unconnected-(P9-Pad35)") (class "Default")
      (node (ref "P9") (pin "35") (pinfunction "35_35") (pintype "bidirectional"))
    )
    (net (code "378") (name "unconnected-(P9-Pad37)") (class "Default")
      (node (ref "P9") (pin "37") (pinfunction "37_37") (pintype "bidirectional"))
    )
    (net (code "379") (name "unconnected-(P9-Pad51)") (class "Default")
      (node (ref "P9") (pin "51") (pinfunction "51_51") (pintype "bidirectional"))
    )
    (net (code "380") (name "unconnected-(P9-Pad52)") (class "Default")
      (node (ref "P9") (pin "52") (pinfunction "52_52") (pintype "bidirectional"))
    )
    (net (code "381") (name "unconnected-(P9-Pad53)") (class "Default")
      (node (ref "P9") (pin "53") (pinfunction "53_53") (pintype "bidirectional"))
    )
    (net (code "382") (name "unconnected-(P9-Pad55)") (class "Default")
      (node (ref "P9") (pin "55") (pinfunction "55_55") (pintype "bidirectional"))
    )
    (net (code "383") (name "unconnected-(P9-Pad70)") (class "Default")
      (node (ref "P9") (pin "70") (pinfunction "70_70") (pintype "bidirectional"))
    )
    (net (code "384") (name "unconnected-(P9-Pad71)") (class "Default")
      (node (ref "P9") (pin "71") (pinfunction "71_71") (pintype "bidirectional"))
    )
    (net (code "385") (name "unconnected-(P10-Pad16)") (class "Default")
      (node (ref "P10") (pin "16") (pinfunction "16_16") (pintype "bidirectional"))
    )
    (net (code "386") (name "unconnected-(P10-Pad17)") (class "Default")
      (node (ref "P10") (pin "17") (pinfunction "17_17") (pintype "bidirectional"))
    )
    (net (code "387") (name "unconnected-(P10-Pad18)") (class "Default")
      (node (ref "P10") (pin "18") (pinfunction "18_18") (pintype "bidirectional"))
    )
    (net (code "388") (name "unconnected-(P10-Pad19)") (class "Default")
      (node (ref "P10") (pin "19") (pinfunction "19_19") (pintype "bidirectional"))
    )
    (net (code "389") (name "unconnected-(P10-Pad20)") (class "Default")
      (node (ref "P10") (pin "20") (pinfunction "20_20") (pintype "bidirectional"))
    )
    (net (code "390") (name "unconnected-(P10-Pad34)") (class "Default")
      (node (ref "P10") (pin "34") (pinfunction "34_34") (pintype "bidirectional"))
    )
    (net (code "391") (name "unconnected-(P10-Pad35)") (class "Default")
      (node (ref "P10") (pin "35") (pinfunction "35_35") (pintype "bidirectional"))
    )
    (net (code "392") (name "unconnected-(P10-Pad37)") (class "Default")
      (node (ref "P10") (pin "37") (pinfunction "37_37") (pintype "bidirectional"))
    )
    (net (code "393") (name "unconnected-(P10-Pad51)") (class "Default")
      (node (ref "P10") (pin "51") (pinfunction "51_51") (pintype "bidirectional"))
    )
    (net (code "394") (name "unconnected-(P10-Pad52)") (class "Default")
      (node (ref "P10") (pin "52") (pinfunction "52_52") (pintype "bidirectional"))
    )
    (net (code "395") (name "unconnected-(P10-Pad53)") (class "Default")
      (node (ref "P10") (pin "53") (pinfunction "53_53") (pintype "bidirectional"))
    )
    (net (code "396") (name "unconnected-(P10-Pad55)") (class "Default")
      (node (ref "P10") (pin "55") (pinfunction "55_55") (pintype "bidirectional"))
    )
    (net (code "397") (name "unconnected-(P10-Pad70)") (class "Default")
      (node (ref "P10") (pin "70") (pinfunction "70_70") (pintype "bidirectional"))
    )
    (net (code "398") (name "unconnected-(P10-Pad71)") (class "Default")
      (node (ref "P10") (pin "71") (pinfunction "71_71") (pintype "bidirectional"))
    )
    (net (code "399") (name "unconnected-(P11-Pad16)") (class "Default")
      (node (ref "P11") (pin "16") (pinfunction "16_16") (pintype "bidirectional"))
    )
    (net (code "400") (name "unconnected-(P11-Pad17)") (class "Default")
      (node (ref "P11") (pin "17") (pinfunction "17_17") (pintype "bidirectional"))
    )
    (net (code "401") (name "unconnected-(P11-Pad18)") (class "Default")
      (node (ref "P11") (pin "18") (pinfunction "18_18") (pintype "bidirectional"))
    )
    (net (code "402") (name "unconnected-(P11-Pad19)") (class "Default")
      (node (ref "P11") (pin "19") (pinfunction "19_19") (pintype "bidirectional"))
    )
    (net (code "403") (name "unconnected-(P11-Pad20)") (class "Default")
      (node (ref "P11") (pin "20") (pinfunction "20_20") (pintype "bidirectional"))
    )
    (net (code "404") (name "unconnected-(P11-Pad34)") (class "Default")
      (node (ref "P11") (pin "34") (pinfunction "34_34") (pintype "bidirectional"))
    )
    (net (code "405") (name "unconnected-(P11-Pad35)") (class "Default")
      (node (ref "P11") (pin "35") (pinfunction "35_35") (pintype "bidirectional"))
    )
    (net (code "406") (name "unconnected-(P11-Pad37)") (class "Default")
      (node (ref "P11") (pin "37") (pinfunction "37_37") (pintype "bidirectional"))
    )
    (net (code "407") (name "unconnected-(P11-Pad51)") (class "Default")
      (node (ref "P11") (pin "51") (pinfunction "51_51") (pintype "bidirectional"))
    )
    (net (code "408") (name "unconnected-(P11-Pad52)") (class "Default")
      (node (ref "P11") (pin "52") (pinfunction "52_52") (pintype "bidirectional"))
    )
    (net (code "409") (name "unconnected-(P11-Pad53)") (class "Default")
      (node (ref "P11") (pin "53") (pinfunction "53_53") (pintype "bidirectional"))
    )
    (net (code "410") (name "unconnected-(P11-Pad55)") (class "Default")
      (node (ref "P11") (pin "55") (pinfunction "55_55") (pintype "bidirectional"))
    )
    (net (code "411") (name "unconnected-(P11-Pad70)") (class "Default")
      (node (ref "P11") (pin "70") (pinfunction "70_70") (pintype "bidirectional"))
    )
    (net (code "412") (name "unconnected-(P11-Pad71)") (class "Default")
      (node (ref "P11") (pin "71") (pinfunction "71_71") (pintype "bidirectional"))
    )
    (net (code "413") (name "unconnected-(P12-Pad16)") (class "Default")
      (node (ref "P12") (pin "16") (pinfunction "16_16") (pintype "bidirectional"))
    )
    (net (code "414") (name "unconnected-(P12-Pad17)") (class "Default")
      (node (ref "P12") (pin "17") (pinfunction "17_17") (pintype "bidirectional"))
    )
    (net (code "415") (name "unconnected-(P12-Pad18)") (class "Default")
      (node (ref "P12") (pin "18") (pinfunction "18_18") (pintype "bidirectional"))
    )
    (net (code "416") (name "unconnected-(P12-Pad19)") (class "Default")
      (node (ref "P12") (pin "19") (pinfunction "19_19") (pintype "bidirectional"))
    )
    (net (code "417") (name "unconnected-(P12-Pad20)") (class "Default")
      (node (ref "P12") (pin "20") (pinfunction "20_20") (pintype "bidirectional"))
    )
    (net (code "418") (name "unconnected-(P12-Pad34)") (class "Default")
      (node (ref "P12") (pin "34") (pinfunction "34_34") (pintype "bidirectional"))
    )
    (net (code "419") (name "unconnected-(P12-Pad35)") (class "Default")
      (node (ref "P12") (pin "35") (pinfunction "35_35") (pintype "bidirectional"))
    )
    (net (code "420") (name "unconnected-(P12-Pad37)") (class "Default")
      (node (ref "P12") (pin "37") (pinfunction "37_37") (pintype "bidirectional"))
    )
    (net (code "421") (name "unconnected-(P12-Pad51)") (class "Default")
      (node (ref "P12") (pin "51") (pinfunction "51_51") (pintype "bidirectional"))
    )
    (net (code "422") (name "unconnected-(P12-Pad52)") (class "Default")
      (node (ref "P12") (pin "52") (pinfunction "52_52") (pintype "bidirectional"))
    )
    (net (code "423") (name "unconnected-(P12-Pad53)") (class "Default")
      (node (ref "P12") (pin "53") (pinfunction "53_53") (pintype "bidirectional"))
    )
    (net (code "424") (name "unconnected-(P12-Pad55)") (class "Default")
      (node (ref "P12") (pin "55") (pinfunction "55_55") (pintype "bidirectional"))
    )
    (net (code "425") (name "unconnected-(P12-Pad70)") (class "Default")
      (node (ref "P12") (pin "70") (pinfunction "70_70") (pintype "bidirectional"))
    )
    (net (code "426") (name "unconnected-(P12-Pad71)") (class "Default")
      (node (ref "P12") (pin "71") (pinfunction "71_71") (pintype "bidirectional"))
    )
    (net (code "427") (name "unconnected-(P13-Pad16)") (class "Default")
      (node (ref "P13") (pin "16") (pinfunction "16_16") (pintype "bidirectional"))
    )
    (net (code "428") (name "unconnected-(P13-Pad17)") (class "Default")
      (node (ref "P13") (pin "17") (pinfunction "17_17") (pintype "bidirectional"))
    )
    (net (code "429") (name "unconnected-(P13-Pad18)") (class "Default")
      (node (ref "P13") (pin "18") (pinfunction "18_18") (pintype "bidirectional"))
    )
    (net (code "430") (name "unconnected-(P13-Pad19)") (class "Default")
      (node (ref "P13") (pin "19") (pinfunction "19_19") (pintype "bidirectional"))
    )
    (net (code "431") (name "unconnected-(P13-Pad20)") (class "Default")
      (node (ref "P13") (pin "20") (pinfunction "20_20") (pintype "bidirectional"))
    )
    (net (code "432") (name "unconnected-(P13-Pad34)") (class "Default")
      (node (ref "P13") (pin "34") (pinfunction "34_34") (pintype "bidirectional"))
    )
    (net (code "433") (name "unconnected-(P13-Pad35)") (class "Default")
      (node (ref "P13") (pin "35") (pinfunction "35_35") (pintype "bidirectional"))
    )
    (net (code "434") (name "unconnected-(P13-Pad37)") (class "Default")
      (node (ref "P13") (pin "37") (pinfunction "37_37") (pintype "bidirectional"))
    )
    (net (code "435") (name "unconnected-(P13-Pad51)") (class "Default")
      (node (ref "P13") (pin "51") (pinfunction "51_51") (pintype "bidirectional"))
    )
    (net (code "436") (name "unconnected-(P13-Pad52)") (class "Default")
      (node (ref "P13") (pin "52") (pinfunction "52_52") (pintype "bidirectional"))
    )
    (net (code "437") (name "unconnected-(P13-Pad53)") (class "Default")
      (node (ref "P13") (pin "53") (pinfunction "53_53") (pintype "bidirectional"))
    )
    (net (code "438") (name "unconnected-(P13-Pad55)") (class "Default")
      (node (ref "P13") (pin "55") (pinfunction "55_55") (pintype "bidirectional"))
    )
    (net (code "439") (name "unconnected-(P13-Pad70)") (class "Default")
      (node (ref "P13") (pin "70") (pinfunction "70_70") (pintype "bidirectional"))
    )
    (net (code "440") (name "unconnected-(P13-Pad71)") (class "Default")
      (node (ref "P13") (pin "71") (pinfunction "71_71") (pintype "bidirectional"))
    )
    (net (code "441") (name "unconnected-(P14-Pad16)") (class "Default")
      (node (ref "P14") (pin "16") (pinfunction "16_16") (pintype "bidirectional"))
    )
    (net (code "442") (name "unconnected-(P14-Pad17)") (class "Default")
      (node (ref "P14") (pin "17") (pinfunction "17_17") (pintype "bidirectional"))
    )
    (net (code "443") (name "unconnected-(P14-Pad18)") (class "Default")
      (node (ref "P14") (pin "18") (pinfunction "18_18") (pintype "bidirectional"))
    )
    (net (code "444") (name "unconnected-(P14-Pad19)") (class "Default")
      (node (ref "P14") (pin "19") (pinfunction "19_19") (pintype "bidirectional"))
    )
    (net (code "445") (name "unconnected-(P14-Pad20)") (class "Default")
      (node (ref "P14") (pin "20") (pinfunction "20_20") (pintype "bidirectional"))
    )
    (net (code "446") (name "unconnected-(P14-Pad34)") (class "Default")
      (node (ref "P14") (pin "34") (pinfunction "34_34") (pintype "bidirectional"))
    )
    (net (code "447") (name "unconnected-(P14-Pad35)") (class "Default")
      (node (ref "P14") (pin "35") (pinfunction "35_35") (pintype "bidirectional"))
    )
    (net (code "448") (name "unconnected-(P14-Pad37)") (class "Default")
      (node (ref "P14") (pin "37") (pinfunction "37_37") (pintype "bidirectional"))
    )
    (net (code "449") (name "unconnected-(P14-Pad51)") (class "Default")
      (node (ref "P14") (pin "51") (pinfunction "51_51") (pintype "bidirectional"))
    )
    (net (code "450") (name "unconnected-(P14-Pad52)") (class "Default")
      (node (ref "P14") (pin "52") (pinfunction "52_52") (pintype "bidirectional"))
    )
    (net (code "451") (name "unconnected-(P14-Pad53)") (class "Default")
      (node (ref "P14") (pin "53") (pinfunction "53_53") (pintype "bidirectional"))
    )
    (net (code "452") (name "unconnected-(P14-Pad55)") (class "Default")
      (node (ref "P14") (pin "55") (pinfunction "55_55") (pintype "bidirectional"))
    )
    (net (code "453") (name "unconnected-(P14-Pad70)") (class "Default")
      (node (ref "P14") (pin "70") (pinfunction "70_70") (pintype "bidirectional"))
    )
    (net (code "454") (name "unconnected-(P14-Pad71)") (class "Default")
      (node (ref "P14") (pin "71") (pinfunction "71_71") (pintype "bidirectional"))
    )
    (net (code "455") (name "unconnected-(P15-Pad16)") (class "Default")
      (node (ref "P15") (pin "16") (pinfunction "16_16") (pintype "bidirectional"))
    )
    (net (code "456") (name "unconnected-(P15-Pad17)") (class "Default")
      (node (ref "P15") (pin "17") (pinfunction "17_17") (pintype "bidirectional"))
    )
    (net (code "457") (name "unconnected-(P15-Pad18)") (class "Default")
      (node (ref "P15") (pin "18") (pinfunction "18_18") (pintype "bidirectional"))
    )
    (net (code "458") (name "unconnected-(P15-Pad19)") (class "Default")
      (node (ref "P15") (pin "19") (pinfunction "19_19") (pintype "bidirectional"))
    )
    (net (code "459") (name "unconnected-(P15-Pad20)") (class "Default")
      (node (ref "P15") (pin "20") (pinfunction "20_20") (pintype "bidirectional"))
    )
    (net (code "460") (name "unconnected-(P15-Pad34)") (class "Default")
      (node (ref "P15") (pin "34") (pinfunction "34_34") (pintype "bidirectional"))
    )
    (net (code "461") (name "unconnected-(P15-Pad35)") (class "Default")
      (node (ref "P15") (pin "35") (pinfunction "35_35") (pintype "bidirectional"))
    )
    (net (code "462") (name "unconnected-(P15-Pad37)") (class "Default")
      (node (ref "P15") (pin "37") (pinfunction "37_37") (pintype "bidirectional"))
    )
    (net (code "463") (name "unconnected-(P15-Pad51)") (class "Default")
      (node (ref "P15") (pin "51") (pinfunction "51_51") (pintype "bidirectional"))
    )
    (net (code "464") (name "unconnected-(P15-Pad52)") (class "Default")
      (node (ref "P15") (pin "52") (pinfunction "52_52") (pintype "bidirectional"))
    )
    (net (code "465") (name "unconnected-(P15-Pad53)") (class "Default")
      (node (ref "P15") (pin "53") (pinfunction "53_53") (pintype "bidirectional"))
    )
    (net (code "466") (name "unconnected-(P15-Pad55)") (class "Default")
      (node (ref "P15") (pin "55") (pinfunction "55_55") (pintype "bidirectional"))
    )
    (net (code "467") (name "unconnected-(P15-Pad70)") (class "Default")
      (node (ref "P15") (pin "70") (pinfunction "70_70") (pintype "bidirectional"))
    )
    (net (code "468") (name "unconnected-(P15-Pad71)") (class "Default")
      (node (ref "P15") (pin "71") (pinfunction "71_71") (pintype "bidirectional"))
    )
    (net (code "469") (name "unconnected-(P16-Pad18)") (class "Default")
      (node (ref "P16") (pin "18") (pinfunction "18_18") (pintype "bidirectional"))
    )
    (net (code "470") (name "unconnected-(P16-Pad19)") (class "Default")
      (node (ref "P16") (pin "19") (pinfunction "19_19") (pintype "bidirectional"))
    )
    (net (code "471") (name "unconnected-(P16-Pad35)") (class "Default")
      (node (ref "P16") (pin "35") (pinfunction "35_35") (pintype "bidirectional"))
    )
    (net (code "472") (name "unconnected-(P16-Pad69)") (class "Default")
      (node (ref "P16") (pin "69") (pinfunction "69_69") (pintype "bidirectional"))
    )
    (net (code "473") (name "unconnected-(P18-Pad18)") (class "Default")
      (node (ref "P18") (pin "18") (pinfunction "18_18") (pintype "bidirectional"))
    )
    (net (code "474") (name "unconnected-(P18-Pad19)") (class "Default")
      (node (ref "P18") (pin "19") (pinfunction "19_19") (pintype "bidirectional"))
    )
    (net (code "475") (name "unconnected-(P18-Pad20)") (class "Default")
      (node (ref "P18") (pin "20") (pinfunction "20_20") (pintype "bidirectional"))
    )
    (net (code "476") (name "unconnected-(P18-Pad34)") (class "Default")
      (node (ref "P18") (pin "34") (pinfunction "34_34") (pintype "bidirectional"))
    )
    (net (code "477") (name "unconnected-(P18-Pad35)") (class "Default")
      (node (ref "P18") (pin "35") (pinfunction "35_35") (pintype "bidirectional"))
    )
    (net (code "478") (name "unconnected-(P18-Pad55)") (class "Default")
      (node (ref "P18") (pin "55") (pinfunction "55_55") (pintype "bidirectional"))
    )
  )
)
